# as14120_x31_fpga_ddr.net
KiCad netlist of a schematic drawn in Altium Designer
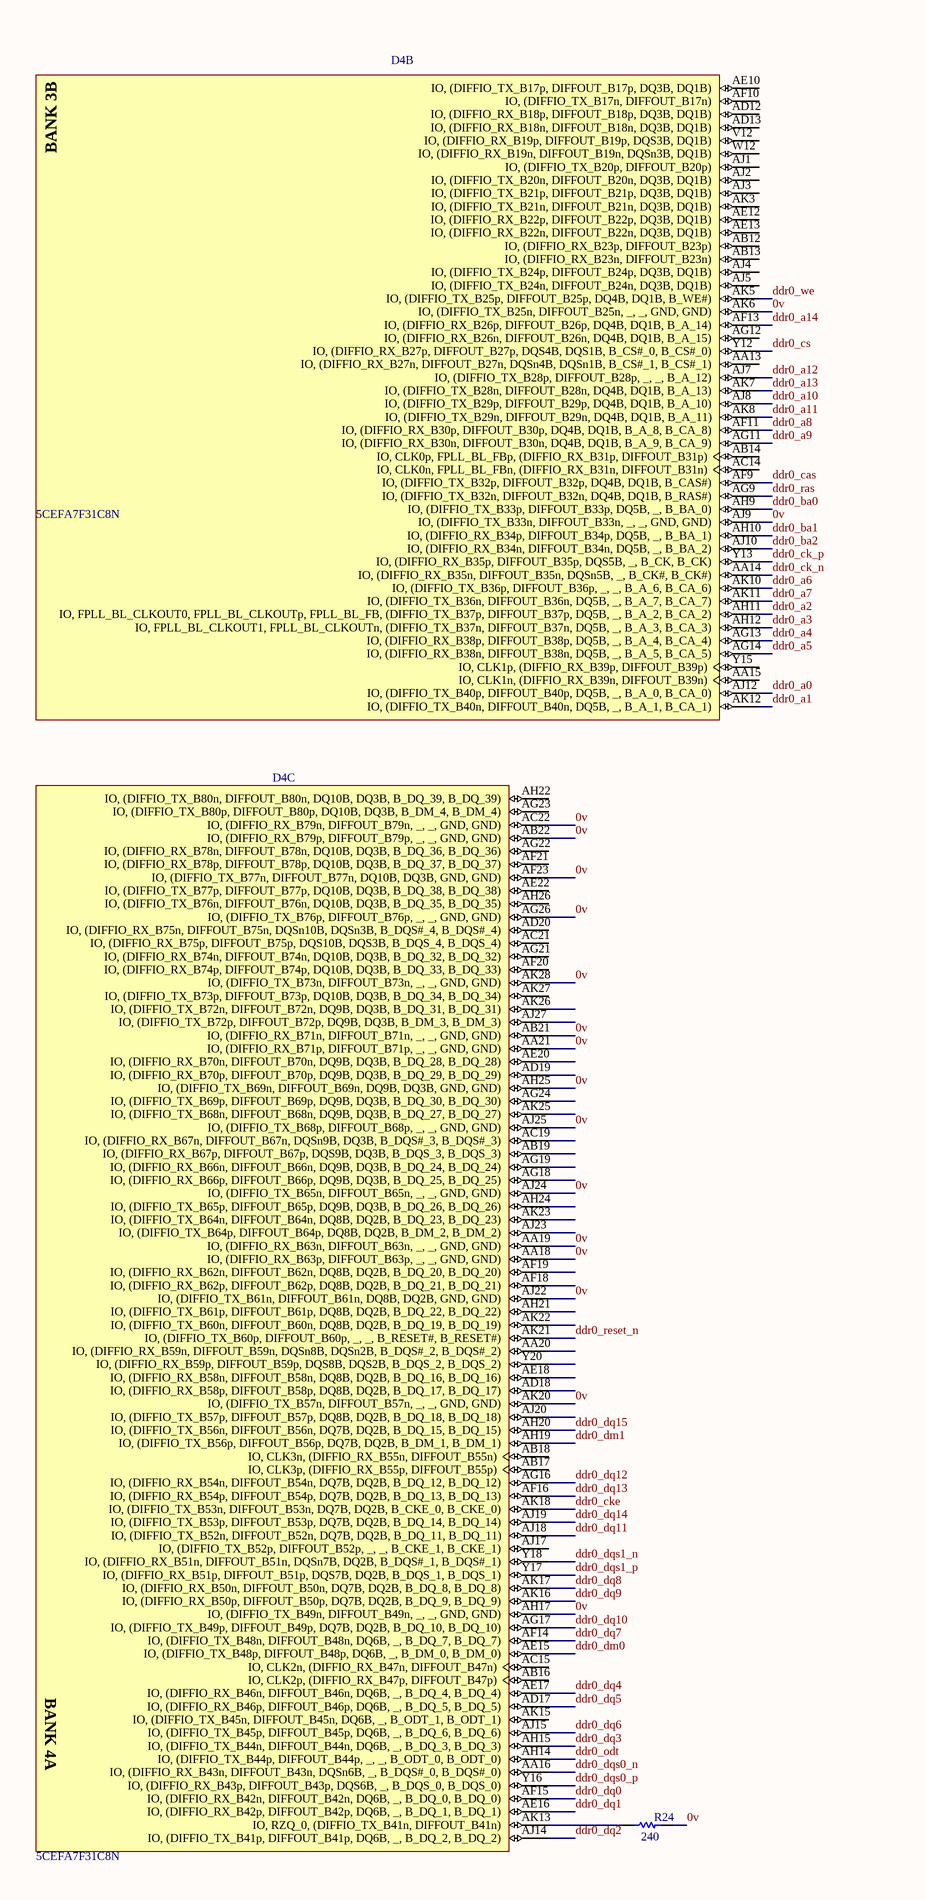
[diagram p0: as14120_x31_fpga_ddr.SchDoc, left]
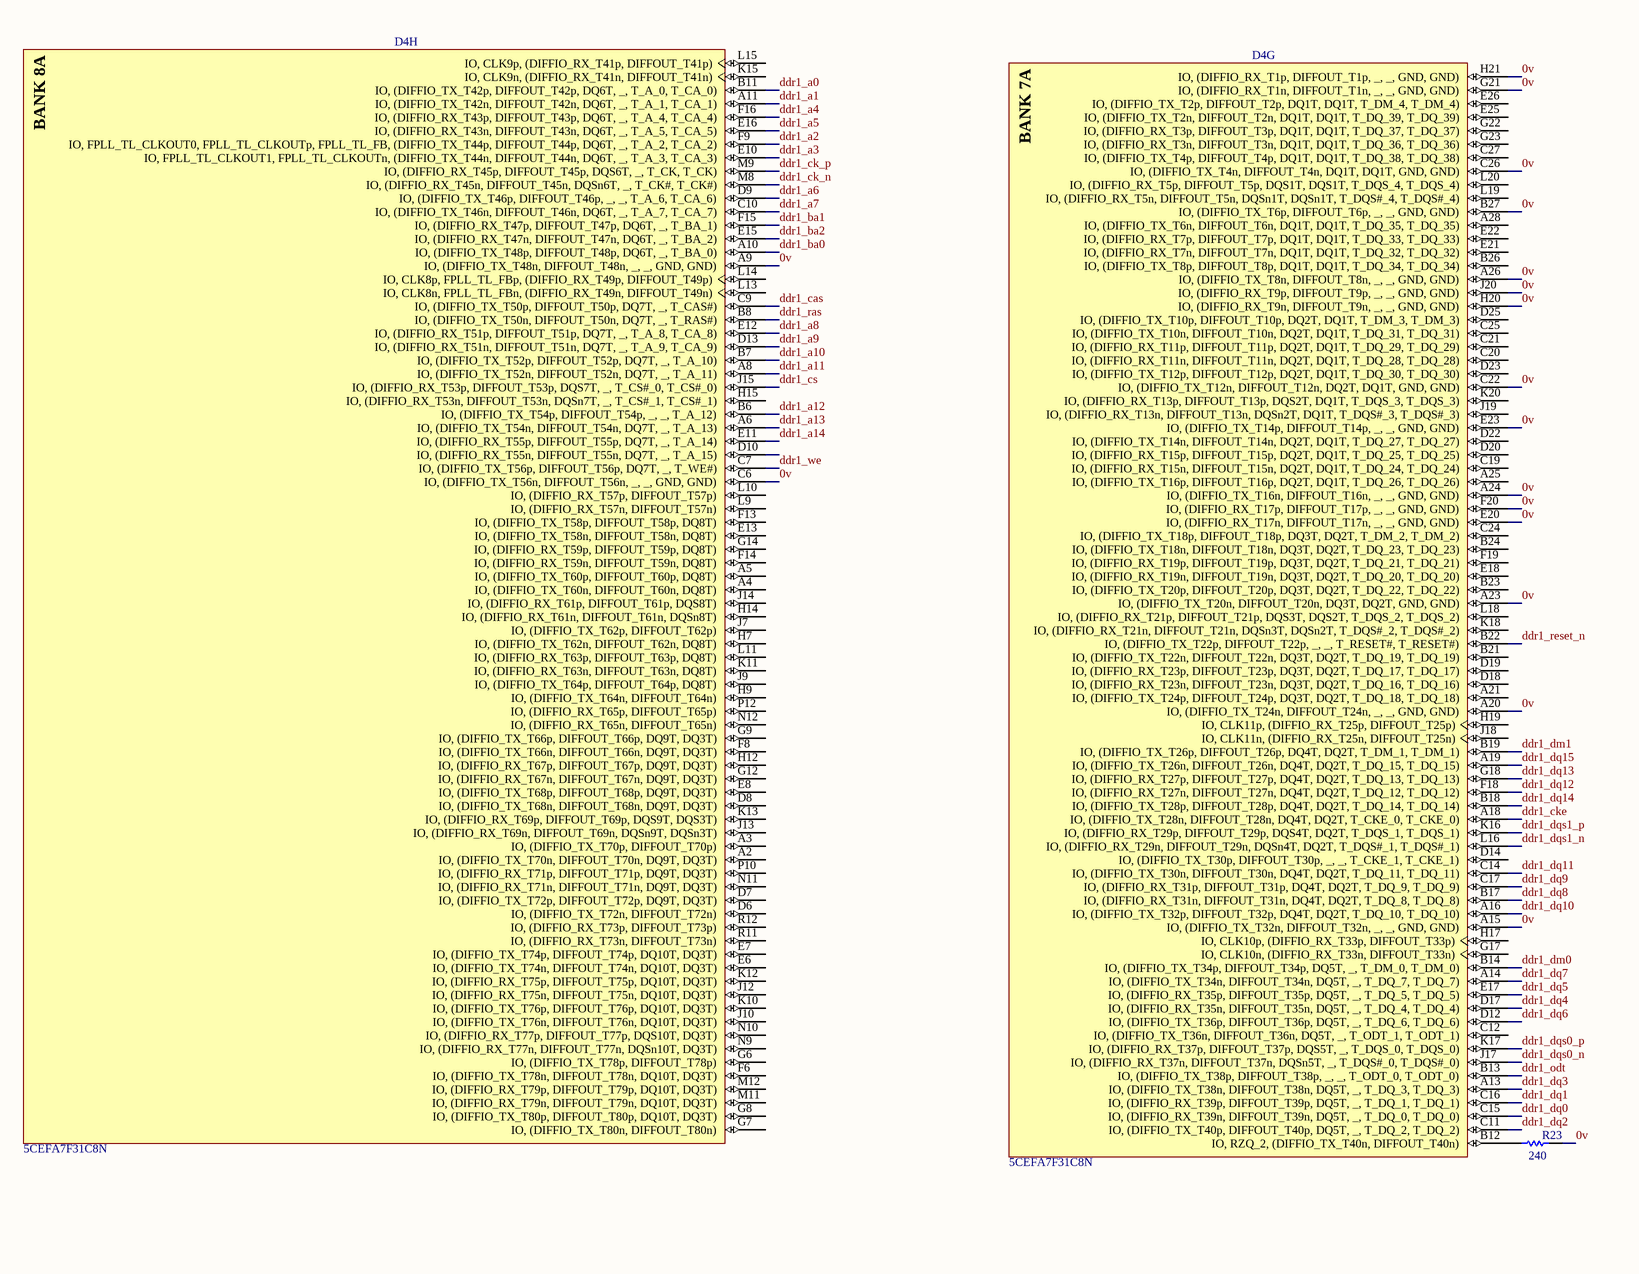
[diagram p1: as14120_x31_fpga_ddr.SchDoc, right]

(export (version "E")
  (design (tool "Eeschema 10.0.6"))
  (components
    (comp (ref "D4")
      (value "5CEFA7F31C8N")
      (footprint "ALTR-896-FBGA-2000A")
      (fields (field (name "MANUFACTURER") "Altera"))
      (libsource (lib "") (part "5CEFA7F31C8N_1"))
    )
    (comp (ref "R23")
      (value "240")
      (footprint "RESC0805(2012)_L")
      (description "1K 0.125W 1% 0805 (2012 Metric)  SMD")
      (fields (field (name "TOLERANCE") "1 %") (field (name "POWER") "0.125 W"))
      (libsource (lib "as14120") (part "RES_0805"))
    )
    (comp (ref "R24")
      (value "240")
      (footprint "RESC0805(2012)_L")
      (description "1K 0.125W 1% 0805 (2012 Metric)  SMD")
      (fields (field (name "TOLERANCE") "1 %") (field (name "POWER") "0.125 W"))
      (libsource (lib "as14120") (part "RES_0805"))
    )
  )
  (nets
    (net (code "1") (name "/0v") (class "Default")
      (node (ref "D4") (pin "A15") (pinfunction "IO,_(DIFFIO_TX_T32n,_DIFFOUT_T32n,__,__,_GND,_GND)_A15") (pintype "bidirectional"))
      (node (ref "D4") (pin "A20") (pinfunction "IO,_(DIFFIO_TX_T24n,_DIFFOUT_T24n,__,__,_GND,_GND)_A20") (pintype "bidirectional"))
      (node (ref "D4") (pin "A23") (pinfunction "IO,_(DIFFIO_TX_T20n,_DIFFOUT_T20n,_DQ3T,_DQ2T,_GND,_GND)_A23") (pintype "bidirectional"))
      (node (ref "D4") (pin "A24") (pinfunction "IO,_(DIFFIO_TX_T16n,_DIFFOUT_T16n,__,__,_GND,_GND)_A24") (pintype "bidirectional"))
      (node (ref "D4") (pin "A26") (pinfunction "IO,_(DIFFIO_TX_T8n,_DIFFOUT_T8n,__,__,_GND,_GND)_A26") (pintype "bidirectional"))
      (node (ref "D4") (pin "A9") (pinfunction "IO,_(DIFFIO_TX_T48n,_DIFFOUT_T48n,__,__,_GND,_GND)_A9") (pintype "bidirectional"))
      (node (ref "D4") (pin "AA18") (pinfunction "IO,_(DIFFIO_RX_B63p,_DIFFOUT_B63p,__,__,_GND,_GND)_AA18") (pintype "bidirectional"))
      (node (ref "D4") (pin "AA19") (pinfunction "IO,_(DIFFIO_RX_B63n,_DIFFOUT_B63n,__,__,_GND,_GND)_AA19") (pintype "bidirectional"))
      (node (ref "D4") (pin "AA21") (pinfunction "IO,_(DIFFIO_RX_B71p,_DIFFOUT_B71p,__,__,_GND,_GND)_AA21") (pintype "bidirectional"))
      (node (ref "D4") (pin "AB21") (pinfunction "IO,_(DIFFIO_RX_B71n,_DIFFOUT_B71n,__,__,_GND,_GND)_AB21") (pintype "bidirectional"))
      (node (ref "D4") (pin "AB22") (pinfunction "IO,_(DIFFIO_RX_B79p,_DIFFOUT_B79p,__,__,_GND,_GND)_AB22") (pintype "bidirectional"))
      (node (ref "D4") (pin "AC22") (pinfunction "IO,_(DIFFIO_RX_B79n,_DIFFOUT_B79n,__,__,_GND,_GND)_AC22") (pintype "bidirectional"))
      (node (ref "D4") (pin "AF23") (pinfunction "IO,_(DIFFIO_TX_B77n,_DIFFOUT_B77n,_DQ10B,_DQ3B,_GND,_GND)_AF23") (pintype "bidirectional"))
      (node (ref "D4") (pin "AG26") (pinfunction "IO,_(DIFFIO_TX_B76p,_DIFFOUT_B76p,__,__,_GND,_GND)_AG26") (pintype "bidirectional"))
      (node (ref "D4") (pin "AH17") (pinfunction "IO,_(DIFFIO_TX_B49n,_DIFFOUT_B49n,__,__,_GND,_GND)_AH17") (pintype "bidirectional"))
      (node (ref "D4") (pin "AH25") (pinfunction "IO,_(DIFFIO_TX_B69n,_DIFFOUT_B69n,_DQ9B,_DQ3B,_GND,_GND)_AH25") (pintype "bidirectional"))
      (node (ref "D4") (pin "AJ22") (pinfunction "IO,_(DIFFIO_TX_B61n,_DIFFOUT_B61n,_DQ8B,_DQ2B,_GND,_GND)_AJ22") (pintype "bidirectional"))
      (node (ref "D4") (pin "AJ24") (pinfunction "IO,_(DIFFIO_TX_B65n,_DIFFOUT_B65n,__,__,_GND,_GND)_AJ24") (pintype "bidirectional"))
      (node (ref "D4") (pin "AJ25") (pinfunction "IO,_(DIFFIO_TX_B68p,_DIFFOUT_B68p,__,__,_GND,_GND)_AJ25") (pintype "bidirectional"))
      (node (ref "D4") (pin "AJ9") (pinfunction "IO,_(DIFFIO_TX_B33n,_DIFFOUT_B33n,__,__,_GND,_GND)_AJ9") (pintype "bidirectional"))
      (node (ref "D4") (pin "AK20") (pinfunction "IO,_(DIFFIO_TX_B57n,_DIFFOUT_B57n,__,__,_GND,_GND)_AK20") (pintype "bidirectional"))
      (node (ref "D4") (pin "AK28") (pinfunction "IO,_(DIFFIO_TX_B73n,_DIFFOUT_B73n,__,__,_GND,_GND)_AK28") (pintype "bidirectional"))
      (node (ref "D4") (pin "AK6") (pinfunction "IO,_(DIFFIO_TX_B25n,_DIFFOUT_B25n,__,__,_GND,_GND)_AK6") (pintype "bidirectional"))
      (node (ref "D4") (pin "B27") (pinfunction "IO,_(DIFFIO_TX_T6p,_DIFFOUT_T6p,__,__,_GND,_GND)_B27") (pintype "bidirectional"))
      (node (ref "D4") (pin "C22") (pinfunction "IO,_(DIFFIO_TX_T12n,_DIFFOUT_T12n,_DQ2T,_DQ1T,_GND,_GND)_C22") (pintype "bidirectional"))
      (node (ref "D4") (pin "C26") (pinfunction "IO,_(DIFFIO_TX_T4n,_DIFFOUT_T4n,_DQ1T,_DQ1T,_GND,_GND)_C26") (pintype "bidirectional"))
      (node (ref "D4") (pin "C6") (pinfunction "IO,_(DIFFIO_TX_T56n,_DIFFOUT_T56n,__,__,_GND,_GND)_C6") (pintype "bidirectional"))
      (node (ref "D4") (pin "E20") (pinfunction "IO,_(DIFFIO_RX_T17n,_DIFFOUT_T17n,__,__,_GND,_GND)_E20") (pintype "bidirectional"))
      (node (ref "D4") (pin "E23") (pinfunction "IO,_(DIFFIO_TX_T14p,_DIFFOUT_T14p,__,__,_GND,_GND)_E23") (pintype "bidirectional"))
      (node (ref "D4") (pin "F20") (pinfunction "IO,_(DIFFIO_RX_T17p,_DIFFOUT_T17p,__,__,_GND,_GND)_F20") (pintype "bidirectional"))
      (node (ref "D4") (pin "G21") (pinfunction "IO,_(DIFFIO_RX_T1n,_DIFFOUT_T1n,__,__,_GND,_GND)_G21") (pintype "bidirectional"))
      (node (ref "D4") (pin "H20") (pinfunction "IO,_(DIFFIO_RX_T9n,_DIFFOUT_T9n,__,__,_GND,_GND)_H20") (pintype "bidirectional"))
      (node (ref "D4") (pin "H21") (pinfunction "IO,_(DIFFIO_RX_T1p,_DIFFOUT_T1p,__,__,_GND,_GND)_H21") (pintype "bidirectional"))
      (node (ref "D4") (pin "J20") (pinfunction "IO,_(DIFFIO_RX_T9p,_DIFFOUT_T9p,__,__,_GND,_GND)_J20") (pintype "bidirectional"))
      (node (ref "R23") (pin "2") (pinfunction "2_2") (pintype "passive"))
      (node (ref "R24") (pin "2") (pinfunction "2_2") (pintype "passive"))
    )
    (net (code "2") (name "/ddr0_a0") (class "Default")
      (node (ref "D4") (pin "AJ12") (pinfunction "IO,_(DIFFIO_TX_B40p,_DIFFOUT_B40p,_DQ5B,__,_B_A_0,_B_CA_0)_AJ12") (pintype "bidirectional"))
    )
    (net (code "3") (name "/ddr0_a1") (class "Default")
      (node (ref "D4") (pin "AK12") (pinfunction "IO,_(DIFFIO_TX_B40n,_DIFFOUT_B40n,_DQ5B,__,_B_A_1,_B_CA_1)_AK12") (pintype "bidirectional"))
    )
    (net (code "4") (name "/ddr0_a2") (class "Default")
      (node (ref "D4") (pin "AH11") (pinfunction "IO,_FPLL_BL_CLKOUT0,_FPLL_BL_CLKOUTp,_FPLL_BL_FB,_(DIFFIO_TX_B37p,_DIFFOUT_B37p,_DQ5B,__,_B_A_2,_B_CA_2)_AH11") (pintype "bidirectional"))
    )
    (net (code "5") (name "/ddr0_a3") (class "Default")
      (node (ref "D4") (pin "AH12") (pinfunction "IO,_FPLL_BL_CLKOUT1,_FPLL_BL_CLKOUTn,_(DIFFIO_TX_B37n,_DIFFOUT_B37n,_DQ5B,__,_B_A_3,_B_CA_3)_AH12") (pintype "bidirectional"))
    )
    (net (code "6") (name "/ddr0_a4") (class "Default")
      (node (ref "D4") (pin "AG13") (pinfunction "IO,_(DIFFIO_RX_B38p,_DIFFOUT_B38p,_DQ5B,__,_B_A_4,_B_CA_4)_AG13") (pintype "bidirectional"))
    )
    (net (code "7") (name "/ddr0_a5") (class "Default")
      (node (ref "D4") (pin "AG14") (pinfunction "IO,_(DIFFIO_RX_B38n,_DIFFOUT_B38n,_DQ5B,__,_B_A_5,_B_CA_5)_AG14") (pintype "bidirectional"))
    )
    (net (code "8") (name "/ddr0_a6") (class "Default")
      (node (ref "D4") (pin "AK10") (pinfunction "IO,_(DIFFIO_TX_B36p,_DIFFOUT_B36p,__,__,_B_A_6,_B_CA_6)_AK10") (pintype "bidirectional"))
    )
    (net (code "9") (name "/ddr0_a7") (class "Default")
      (node (ref "D4") (pin "AK11") (pinfunction "IO,_(DIFFIO_TX_B36n,_DIFFOUT_B36n,_DQ5B,__,_B_A_7,_B_CA_7)_AK11") (pintype "bidirectional"))
    )
    (net (code "10") (name "/ddr0_a8") (class "Default")
      (node (ref "D4") (pin "AF11") (pinfunction "IO,_(DIFFIO_RX_B30p,_DIFFOUT_B30p,_DQ4B,_DQ1B,_B_A_8,_B_CA_8)_AF11") (pintype "bidirectional"))
    )
    (net (code "11") (name "/ddr0_a9") (class "Default")
      (node (ref "D4") (pin "AG11") (pinfunction "IO,_(DIFFIO_RX_B30n,_DIFFOUT_B30n,_DQ4B,_DQ1B,_B_A_9,_B_CA_9)_AG11") (pintype "bidirectional"))
    )
    (net (code "12") (name "/ddr0_a10") (class "Default")
      (node (ref "D4") (pin "AJ8") (pinfunction "IO,_(DIFFIO_TX_B29p,_DIFFOUT_B29p,_DQ4B,_DQ1B,_B_A_10)_AJ8") (pintype "bidirectional"))
    )
    (net (code "13") (name "/ddr0_a11") (class "Default")
      (node (ref "D4") (pin "AK8") (pinfunction "IO,_(DIFFIO_TX_B29n,_DIFFOUT_B29n,_DQ4B,_DQ1B,_B_A_11)_AK8") (pintype "bidirectional"))
    )
    (net (code "14") (name "/ddr0_a12") (class "Default")
      (node (ref "D4") (pin "AJ7") (pinfunction "IO,_(DIFFIO_TX_B28p,_DIFFOUT_B28p,__,__,_B_A_12)_AJ7") (pintype "bidirectional"))
    )
    (net (code "15") (name "/ddr0_a13") (class "Default")
      (node (ref "D4") (pin "AK7") (pinfunction "IO,_(DIFFIO_TX_B28n,_DIFFOUT_B28n,_DQ4B,_DQ1B,_B_A_13)_AK7") (pintype "bidirectional"))
    )
    (net (code "16") (name "/ddr0_a14") (class "Default")
      (node (ref "D4") (pin "AF13") (pinfunction "IO,_(DIFFIO_RX_B26p,_DIFFOUT_B26p,_DQ4B,_DQ1B,_B_A_14)_AF13") (pintype "bidirectional"))
    )
    (net (code "17") (name "/ddr0_ba0") (class "Default")
      (node (ref "D4") (pin "AH9") (pinfunction "IO,_(DIFFIO_TX_B33p,_DIFFOUT_B33p,_DQ5B,__,_B_BA_0)_AH9") (pintype "bidirectional"))
    )
    (net (code "18") (name "/ddr0_ba1") (class "Default")
      (node (ref "D4") (pin "AH10") (pinfunction "IO,_(DIFFIO_RX_B34p,_DIFFOUT_B34p,_DQ5B,__,_B_BA_1)_AH10") (pintype "bidirectional"))
    )
    (net (code "19") (name "/ddr0_ba2") (class "Default")
      (node (ref "D4") (pin "AJ10") (pinfunction "IO,_(DIFFIO_RX_B34n,_DIFFOUT_B34n,_DQ5B,__,_B_BA_2)_AJ10") (pintype "bidirectional"))
    )
    (net (code "20") (name "/ddr0_cas") (class "Default")
      (node (ref "D4") (pin "AF9") (pinfunction "IO,_(DIFFIO_TX_B32p,_DIFFOUT_B32p,_DQ4B,_DQ1B,_B_CAS#)_AF9") (pintype "bidirectional"))
    )
    (net (code "21") (name "/ddr0_ck_n") (class "Default")
      (node (ref "D4") (pin "AA14") (pinfunction "IO,_(DIFFIO_RX_B35n,_DIFFOUT_B35n,_DQSn5B,__,_B_CK#,_B_CK#)_AA14") (pintype "bidirectional"))
    )
    (net (code "22") (name "/ddr0_ck_p") (class "Default")
      (node (ref "D4") (pin "Y13") (pinfunction "IO,_(DIFFIO_RX_B35p,_DIFFOUT_B35p,_DQS5B,__,_B_CK,_B_CK)_Y13") (pintype "bidirectional"))
    )
    (net (code "23") (name "/ddr0_cke") (class "Default")
      (node (ref "D4") (pin "AK18") (pinfunction "IO,_(DIFFIO_TX_B53n,_DIFFOUT_B53n,_DQ7B,_DQ2B,_B_CKE_0,_B_CKE_0)_AK18") (pintype "bidirectional"))
    )
    (net (code "24") (name "/ddr0_cs") (class "Default")
      (node (ref "D4") (pin "Y12") (pinfunction "IO,_(DIFFIO_RX_B27p,_DIFFOUT_B27p,_DQS4B,_DQS1B,_B_CS#_0,_B_CS#_0)_Y12") (pintype "bidirectional"))
    )
    (net (code "25") (name "/ddr0_dm0") (class "Default")
      (node (ref "D4") (pin "AE15") (pinfunction "IO,_(DIFFIO_TX_B48p,_DIFFOUT_B48p,_DQ6B,__,_B_DM_0,_B_DM_0)_AE15") (pintype "bidirectional"))
    )
    (net (code "26") (name "/ddr0_dm1") (class "Default")
      (node (ref "D4") (pin "AH19") (pinfunction "IO,_(DIFFIO_TX_B56p,_DIFFOUT_B56p,_DQ7B,_DQ2B,_B_DM_1,_B_DM_1)_AH19") (pintype "bidirectional"))
    )
    (net (code "27") (name "/ddr0_dq0") (class "Default")
      (node (ref "D4") (pin "AF15") (pinfunction "IO,_(DIFFIO_RX_B42n,_DIFFOUT_B42n,_DQ6B,__,_B_DQ_0,_B_DQ_0)_AF15") (pintype "bidirectional"))
    )
    (net (code "28") (name "/ddr0_dq1") (class "Default")
      (node (ref "D4") (pin "AE16") (pinfunction "IO,_(DIFFIO_RX_B42p,_DIFFOUT_B42p,_DQ6B,__,_B_DQ_1,_B_DQ_1)_AE16") (pintype "bidirectional"))
    )
    (net (code "29") (name "/ddr0_dq2") (class "Default")
      (node (ref "D4") (pin "AJ14") (pinfunction "IO,_(DIFFIO_TX_B41p,_DIFFOUT_B41p,_DQ6B,__,_B_DQ_2,_B_DQ_2)_AJ14") (pintype "bidirectional"))
    )
    (net (code "30") (name "/ddr0_dq3") (class "Default")
      (node (ref "D4") (pin "AH15") (pinfunction "IO,_(DIFFIO_TX_B44n,_DIFFOUT_B44n,_DQ6B,__,_B_DQ_3,_B_DQ_3)_AH15") (pintype "bidirectional"))
    )
    (net (code "31") (name "/ddr0_dq4") (class "Default")
      (node (ref "D4") (pin "AE17") (pinfunction "IO,_(DIFFIO_RX_B46n,_DIFFOUT_B46n,_DQ6B,__,_B_DQ_4,_B_DQ_4)_AE17") (pintype "bidirectional"))
    )
    (net (code "32") (name "/ddr0_dq5") (class "Default")
      (node (ref "D4") (pin "AD17") (pinfunction "IO,_(DIFFIO_RX_B46p,_DIFFOUT_B46p,_DQ6B,__,_B_DQ_5,_B_DQ_5)_AD17") (pintype "bidirectional"))
    )
    (net (code "33") (name "/ddr0_dq6") (class "Default")
      (node (ref "D4") (pin "AJ15") (pinfunction "IO,_(DIFFIO_TX_B45p,_DIFFOUT_B45p,_DQ6B,__,_B_DQ_6,_B_DQ_6)_AJ15") (pintype "bidirectional"))
    )
    (net (code "34") (name "/ddr0_dq7") (class "Default")
      (node (ref "D4") (pin "AF14") (pinfunction "IO,_(DIFFIO_TX_B48n,_DIFFOUT_B48n,_DQ6B,__,_B_DQ_7,_B_DQ_7)_AF14") (pintype "bidirectional"))
    )
    (net (code "35") (name "/ddr0_dq8") (class "Default")
      (node (ref "D4") (pin "AK17") (pinfunction "IO,_(DIFFIO_RX_B50n,_DIFFOUT_B50n,_DQ7B,_DQ2B,_B_DQ_8,_B_DQ_8)_AK17") (pintype "bidirectional"))
    )
    (net (code "36") (name "/ddr0_dq9") (class "Default")
      (node (ref "D4") (pin "AK16") (pinfunction "IO,_(DIFFIO_RX_B50p,_DIFFOUT_B50p,_DQ7B,_DQ2B,_B_DQ_9,_B_DQ_9)_AK16") (pintype "bidirectional"))
    )
    (net (code "37") (name "/ddr0_dq10") (class "Default")
      (node (ref "D4") (pin "AG17") (pinfunction "IO,_(DIFFIO_TX_B49p,_DIFFOUT_B49p,_DQ7B,_DQ2B,_B_DQ_10,_B_DQ_10)_AG17") (pintype "bidirectional"))
    )
    (net (code "38") (name "/ddr0_dq11") (class "Default")
      (node (ref "D4") (pin "AJ18") (pinfunction "IO,_(DIFFIO_TX_B52n,_DIFFOUT_B52n,_DQ7B,_DQ2B,_B_DQ_11,_B_DQ_11)_AJ18") (pintype "bidirectional"))
    )
    (net (code "39") (name "/ddr0_dq12") (class "Default")
      (node (ref "D4") (pin "AG16") (pinfunction "IO,_(DIFFIO_RX_B54n,_DIFFOUT_B54n,_DQ7B,_DQ2B,_B_DQ_12,_B_DQ_12)_AG16") (pintype "bidirectional"))
    )
    (net (code "40") (name "/ddr0_dq13") (class "Default")
      (node (ref "D4") (pin "AF16") (pinfunction "IO,_(DIFFIO_RX_B54p,_DIFFOUT_B54p,_DQ7B,_DQ2B,_B_DQ_13,_B_DQ_13)_AF16") (pintype "bidirectional"))
    )
    (net (code "41") (name "/ddr0_dq14") (class "Default")
      (node (ref "D4") (pin "AJ19") (pinfunction "IO,_(DIFFIO_TX_B53p,_DIFFOUT_B53p,_DQ7B,_DQ2B,_B_DQ_14,_B_DQ_14)_AJ19") (pintype "bidirectional"))
    )
    (net (code "42") (name "/ddr0_dq15") (class "Default")
      (node (ref "D4") (pin "AH20") (pinfunction "IO,_(DIFFIO_TX_B56n,_DIFFOUT_B56n,_DQ7B,_DQ2B,_B_DQ_15,_B_DQ_15)_AH20") (pintype "bidirectional"))
    )
    (net (code "43") (name "/ddr0_dqs0_n") (class "Default")
      (node (ref "D4") (pin "AA16") (pinfunction "IO,_(DIFFIO_RX_B43n,_DIFFOUT_B43n,_DQSn6B,__,_B_DQS#_0,_B_DQS#_0)_AA16") (pintype "bidirectional"))
    )
    (net (code "44") (name "/ddr0_dqs0_p") (class "Default")
      (node (ref "D4") (pin "Y16") (pinfunction "IO,_(DIFFIO_RX_B43p,_DIFFOUT_B43p,_DQS6B,__,_B_DQS_0,_B_DQS_0)_Y16") (pintype "bidirectional"))
    )
    (net (code "45") (name "/ddr0_dqs1_n") (class "Default")
      (node (ref "D4") (pin "Y18") (pinfunction "IO,_(DIFFIO_RX_B51n,_DIFFOUT_B51n,_DQSn7B,_DQ2B,_B_DQS#_1,_B_DQS#_1)_Y18") (pintype "bidirectional"))
    )
    (net (code "46") (name "/ddr0_dqs1_p") (class "Default")
      (node (ref "D4") (pin "Y17") (pinfunction "IO,_(DIFFIO_RX_B51p,_DIFFOUT_B51p,_DQS7B,_DQ2B,_B_DQS_1,_B_DQS_1)_Y17") (pintype "bidirectional"))
    )
    (net (code "47") (name "/ddr0_odt") (class "Default")
      (node (ref "D4") (pin "AH14") (pinfunction "IO,_(DIFFIO_TX_B44p,_DIFFOUT_B44p,__,__,_B_ODT_0,_B_ODT_0)_AH14") (pintype "bidirectional"))
    )
    (net (code "48") (name "/ddr0_ras") (class "Default")
      (node (ref "D4") (pin "AG9") (pinfunction "IO,_(DIFFIO_TX_B32n,_DIFFOUT_B32n,_DQ4B,_DQ1B,_B_RAS#)_AG9") (pintype "bidirectional"))
    )
    (net (code "49") (name "/ddr0_reset_n") (class "Default")
      (node (ref "D4") (pin "AK21") (pinfunction "IO,_(DIFFIO_TX_B60p,_DIFFOUT_B60p,__,__,_B_RESET#,_B_RESET#)_AK21") (pintype "bidirectional"))
    )
    (net (code "50") (name "/ddr0_we") (class "Default")
      (node (ref "D4") (pin "AK5") (pinfunction "IO,_(DIFFIO_TX_B25p,_DIFFOUT_B25p,_DQ4B,_DQ1B,_B_WE#)_AK5") (pintype "bidirectional"))
    )
    (net (code "51") (name "/ddr1_a0") (class "Default")
      (node (ref "D4") (pin "B11") (pinfunction "IO,_(DIFFIO_TX_T42p,_DIFFOUT_T42p,_DQ6T,__,_T_A_0,_T_CA_0)_B11") (pintype "bidirectional"))
    )
    (net (code "52") (name "/ddr1_a1") (class "Default")
      (node (ref "D4") (pin "A11") (pinfunction "IO,_(DIFFIO_TX_T42n,_DIFFOUT_T42n,_DQ6T,__,_T_A_1,_T_CA_1)_A11") (pintype "bidirectional"))
    )
    (net (code "53") (name "/ddr1_a2") (class "Default")
      (node (ref "D4") (pin "F9") (pinfunction "IO,_FPLL_TL_CLKOUT0,_FPLL_TL_CLKOUTp,_FPLL_TL_FB,_(DIFFIO_TX_T44p,_DIFFOUT_T44p,_DQ6T,__,_T_A_2,_T_CA_2)_F9") (pintype "bidirectional"))
    )
    (net (code "54") (name "/ddr1_a3") (class "Default")
      (node (ref "D4") (pin "E10") (pinfunction "IO,_FPLL_TL_CLKOUT1,_FPLL_TL_CLKOUTn,_(DIFFIO_TX_T44n,_DIFFOUT_T44n,_DQ6T,__,_T_A_3,_T_CA_3)_E10") (pintype "bidirectional"))
    )
    (net (code "55") (name "/ddr1_a4") (class "Default")
      (node (ref "D4") (pin "F16") (pinfunction "IO,_(DIFFIO_RX_T43p,_DIFFOUT_T43p,_DQ6T,__,_T_A_4,_T_CA_4)_F16") (pintype "bidirectional"))
    )
    (net (code "56") (name "/ddr1_a5") (class "Default")
      (node (ref "D4") (pin "E16") (pinfunction "IO,_(DIFFIO_RX_T43n,_DIFFOUT_T43n,_DQ6T,__,_T_A_5,_T_CA_5)_E16") (pintype "bidirectional"))
    )
    (net (code "57") (name "/ddr1_a6") (class "Default")
      (node (ref "D4") (pin "D9") (pinfunction "IO,_(DIFFIO_TX_T46p,_DIFFOUT_T46p,__,__,_T_A_6,_T_CA_6)_D9") (pintype "bidirectional"))
    )
    (net (code "58") (name "/ddr1_a7") (class "Default")
      (node (ref "D4") (pin "C10") (pinfunction "IO,_(DIFFIO_TX_T46n,_DIFFOUT_T46n,_DQ6T,__,_T_A_7,_T_CA_7)_C10") (pintype "bidirectional"))
    )
    (net (code "59") (name "/ddr1_a8") (class "Default")
      (node (ref "D4") (pin "E12") (pinfunction "IO,_(DIFFIO_RX_T51p,_DIFFOUT_T51p,_DQ7T,__,_T_A_8,_T_CA_8)_E12") (pintype "bidirectional"))
    )
    (net (code "60") (name "/ddr1_a9") (class "Default")
      (node (ref "D4") (pin "D13") (pinfunction "IO,_(DIFFIO_RX_T51n,_DIFFOUT_T51n,_DQ7T,__,_T_A_9,_T_CA_9)_D13") (pintype "bidirectional"))
    )
    (net (code "61") (name "/ddr1_a10") (class "Default")
      (node (ref "D4") (pin "B7") (pinfunction "IO,_(DIFFIO_TX_T52p,_DIFFOUT_T52p,_DQ7T,__,_T_A_10)_B7") (pintype "bidirectional"))
    )
    (net (code "62") (name "/ddr1_a11") (class "Default")
      (node (ref "D4") (pin "A8") (pinfunction "IO,_(DIFFIO_TX_T52n,_DIFFOUT_T52n,_DQ7T,__,_T_A_11)_A8") (pintype "bidirectional"))
    )
    (net (code "63") (name "/ddr1_a12") (class "Default")
      (node (ref "D4") (pin "B6") (pinfunction "IO,_(DIFFIO_TX_T54p,_DIFFOUT_T54p,__,__,_T_A_12)_B6") (pintype "bidirectional"))
    )
    (net (code "64") (name "/ddr1_a13") (class "Default")
      (node (ref "D4") (pin "A6") (pinfunction "IO,_(DIFFIO_TX_T54n,_DIFFOUT_T54n,_DQ7T,__,_T_A_13)_A6") (pintype "bidirectional"))
    )
    (net (code "65") (name "/ddr1_a14") (class "Default")
      (node (ref "D4") (pin "E11") (pinfunction "IO,_(DIFFIO_RX_T55p,_DIFFOUT_T55p,_DQ7T,__,_T_A_14)_E11") (pintype "bidirectional"))
    )
    (net (code "66") (name "/ddr1_ba0") (class "Default")
      (node (ref "D4") (pin "A10") (pinfunction "IO,_(DIFFIO_TX_T48p,_DIFFOUT_T48p,_DQ6T,__,_T_BA_0)_A10") (pintype "bidirectional"))
    )
    (net (code "67") (name "/ddr1_ba1") (class "Default")
      (node (ref "D4") (pin "F15") (pinfunction "IO,_(DIFFIO_RX_T47p,_DIFFOUT_T47p,_DQ6T,__,_T_BA_1)_F15") (pintype "bidirectional"))
    )
    (net (code "68") (name "/ddr1_ba2") (class "Default")
      (node (ref "D4") (pin "E15") (pinfunction "IO,_(DIFFIO_RX_T47n,_DIFFOUT_T47n,_DQ6T,__,_T_BA_2)_E15") (pintype "bidirectional"))
    )
    (net (code "69") (name "/ddr1_cas") (class "Default")
      (node (ref "D4") (pin "C9") (pinfunction "IO,_(DIFFIO_TX_T50p,_DIFFOUT_T50p,_DQ7T,__,_T_CAS#)_C9") (pintype "bidirectional"))
    )
    (net (code "70") (name "/ddr1_ck_n") (class "Default")
      (node (ref "D4") (pin "M8") (pinfunction "IO,_(DIFFIO_RX_T45n,_DIFFOUT_T45n,_DQSn6T,__,_T_CK#,_T_CK#)_M8") (pintype "bidirectional"))
    )
    (net (code "71") (name "/ddr1_ck_p") (class "Default")
      (node (ref "D4") (pin "M9") (pinfunction "IO,_(DIFFIO_RX_T45p,_DIFFOUT_T45p,_DQS6T,__,_T_CK,_T_CK)_M9") (pintype "bidirectional"))
    )
    (net (code "72") (name "/ddr1_cke") (class "Default")
      (node (ref "D4") (pin "A18") (pinfunction "IO,_(DIFFIO_TX_T28n,_DIFFOUT_T28n,_DQ4T,_DQ2T,_T_CKE_0,_T_CKE_0)_A18") (pintype "bidirectional"))
    )
    (net (code "73") (name "/ddr1_cs") (class "Default")
      (node (ref "D4") (pin "J15") (pinfunction "IO,_(DIFFIO_RX_T53p,_DIFFOUT_T53p,_DQS7T,__,_T_CS#_0,_T_CS#_0)_J15") (pintype "bidirectional"))
    )
    (net (code "74") (name "/ddr1_dm0") (class "Default")
      (node (ref "D4") (pin "B14") (pinfunction "IO,_(DIFFIO_TX_T34p,_DIFFOUT_T34p,_DQ5T,__,_T_DM_0,_T_DM_0)_B14") (pintype "bidirectional"))
    )
    (net (code "75") (name "/ddr1_dm1") (class "Default")
      (node (ref "D4") (pin "B19") (pinfunction "IO,_(DIFFIO_TX_T26p,_DIFFOUT_T26p,_DQ4T,_DQ2T,_T_DM_1,_T_DM_1)_B19") (pintype "bidirectional"))
    )
    (net (code "76") (name "/ddr1_dq0") (class "Default")
      (node (ref "D4") (pin "C15") (pinfunction "IO,_(DIFFIO_RX_T39n,_DIFFOUT_T39n,_DQ5T,__,_T_DQ_0,_T_DQ_0)_C15") (pintype "bidirectional"))
    )
    (net (code "77") (name "/ddr1_dq1") (class "Default")
      (node (ref "D4") (pin "C16") (pinfunction "IO,_(DIFFIO_RX_T39p,_DIFFOUT_T39p,_DQ5T,__,_T_DQ_1,_T_DQ_1)_C16") (pintype "bidirectional"))
    )
    (net (code "78") (name "/ddr1_dq2") (class "Default")
      (node (ref "D4") (pin "C11") (pinfunction "IO,_(DIFFIO_TX_T40p,_DIFFOUT_T40p,_DQ5T,__,_T_DQ_2,_T_DQ_2)_C11") (pintype "bidirectional"))
    )
    (net (code "79") (name "/ddr1_dq3") (class "Default")
      (node (ref "D4") (pin "A13") (pinfunction "IO,_(DIFFIO_TX_T38n,_DIFFOUT_T38n,_DQ5T,__,_T_DQ_3,_T_DQ_3)_A13") (pintype "bidirectional"))
    )
    (net (code "80") (name "/ddr1_dq4") (class "Default")
      (node (ref "D4") (pin "D17") (pinfunction "IO,_(DIFFIO_RX_T35n,_DIFFOUT_T35n,_DQ5T,__,_T_DQ_4,_T_DQ_4)_D17") (pintype "bidirectional"))
    )
    (net (code "81") (name "/ddr1_dq5") (class "Default")
      (node (ref "D4") (pin "E17") (pinfunction "IO,_(DIFFIO_RX_T35p,_DIFFOUT_T35p,_DQ5T,__,_T_DQ_5,_T_DQ_5)_E17") (pintype "bidirectional"))
    )
    (net (code "82") (name "/ddr1_dq6") (class "Default")
      (node (ref "D4") (pin "D12") (pinfunction "IO,_(DIFFIO_TX_T36p,_DIFFOUT_T36p,_DQ5T,__,_T_DQ_6,_T_DQ_6)_D12") (pintype "bidirectional"))
    )
    (net (code "83") (name "/ddr1_dq7") (class "Default")
      (node (ref "D4") (pin "A14") (pinfunction "IO,_(DIFFIO_TX_T34n,_DIFFOUT_T34n,_DQ5T,__,_T_DQ_7,_T_DQ_7)_A14") (pintype "bidirectional"))
    )
    (net (code "84") (name "/ddr1_dq8") (class "Default")
      (node (ref "D4") (pin "B17") (pinfunction "IO,_(DIFFIO_RX_T31n,_DIFFOUT_T31n,_DQ4T,_DQ2T,_T_DQ_8,_T_DQ_8)_B17") (pintype "bidirectional"))
    )
    (net (code "85") (name "/ddr1_dq9") (class "Default")
      (node (ref "D4") (pin "C17") (pinfunction "IO,_(DIFFIO_RX_T31p,_DIFFOUT_T31p,_DQ4T,_DQ2T,_T_DQ_9,_T_DQ_9)_C17") (pintype "bidirectional"))
    )
    (net (code "86") (name "/ddr1_dq10") (class "Default")
      (node (ref "D4") (pin "A16") (pinfunction "IO,_(DIFFIO_TX_T32p,_DIFFOUT_T32p,_DQ4T,_DQ2T,_T_DQ_10,_T_DQ_10)_A16") (pintype "bidirectional"))
    )
    (net (code "87") (name "/ddr1_dq11") (class "Default")
      (node (ref "D4") (pin "C14") (pinfunction "IO,_(DIFFIO_TX_T30n,_DIFFOUT_T30n,_DQ4T,_DQ2T,_T_DQ_11,_T_DQ_11)_C14") (pintype "bidirectional"))
    )
    (net (code "88") (name "/ddr1_dq12") (class "Default")
      (node (ref "D4") (pin "F18") (pinfunction "IO,_(DIFFIO_RX_T27n,_DIFFOUT_T27n,_DQ4T,_DQ2T,_T_DQ_12,_T_DQ_12)_F18") (pintype "bidirectional"))
    )
    (net (code "89") (name "/ddr1_dq13") (class "Default")
      (node (ref "D4") (pin "G18") (pinfunction "IO,_(DIFFIO_RX_T27p,_DIFFOUT_T27p,_DQ4T,_DQ2T,_T_DQ_13,_T_DQ_13)_G18") (pintype "bidirectional"))
    )
    (net (code "90") (name "/ddr1_dq14") (class "Default")
      (node (ref "D4") (pin "B18") (pinfunction "IO,_(DIFFIO_TX_T28p,_DIFFOUT_T28p,_DQ4T,_DQ2T,_T_DQ_14,_T_DQ_14)_B18") (pintype "bidirectional"))
    )
    (net (code "91") (name "/ddr1_dq15") (class "Default")
      (node (ref "D4") (pin "A19") (pinfunction "IO,_(DIFFIO_TX_T26n,_DIFFOUT_T26n,_DQ4T,_DQ2T,_T_DQ_15,_T_DQ_15)_A19") (pintype "bidirectional"))
    )
    (net (code "92") (name "/ddr1_dqs0_n") (class "Default")
      (node (ref "D4") (pin "J17") (pinfunction "IO,_(DIFFIO_RX_T37n,_DIFFOUT_T37n,_DQSn5T,__,_T_DQS#_0,_T_DQS#_0)_J17") (pintype "bidirectional"))
    )
    (net (code "93") (name "/ddr1_dqs0_p") (class "Default")
      (node (ref "D4") (pin "K17") (pinfunction "IO,_(DIFFIO_RX_T37p,_DIFFOUT_T37p,_DQS5T,__,_T_DQS_0,_T_DQS_0)_K17") (pintype "bidirectional"))
    )
    (net (code "94") (name "/ddr1_dqs1_n") (class "Default")
      (node (ref "D4") (pin "L16") (pinfunction "IO,_(DIFFIO_RX_T29n,_DIFFOUT_T29n,_DQSn4T,_DQ2T,_T_DQS#_1,_T_DQS#_1)_L16") (pintype "bidirectional"))
    )
    (net (code "95") (name "/ddr1_dqs1_p") (class "Default")
      (node (ref "D4") (pin "K16") (pinfunction "IO,_(DIFFIO_RX_T29p,_DIFFOUT_T29p,_DQS4T,_DQ2T,_T_DQS_1,_T_DQS_1)_K16") (pintype "bidirectional"))
    )
    (net (code "96") (name "/ddr1_odt") (class "Default")
      (node (ref "D4") (pin "B13") (pinfunction "IO,_(DIFFIO_TX_T38p,_DIFFOUT_T38p,__,__,_T_ODT_0,_T_ODT_0)_B13") (pintype "bidirectional"))
    )
    (net (code "97") (name "/ddr1_ras") (class "Default")
      (node (ref "D4") (pin "B8") (pinfunction "IO,_(DIFFIO_TX_T50n,_DIFFOUT_T50n,_DQ7T,__,_T_RAS#)_B8") (pintype "bidirectional"))
    )
    (net (code "98") (name "/ddr1_reset_n") (class "Default")
      (node (ref "D4") (pin "B22") (pinfunction "IO,_(DIFFIO_TX_T22p,_DIFFOUT_T22p,__,__,_T_RESET#,_T_RESET#)_B22") (pintype "bidirectional"))
    )
    (net (code "99") (name "/ddr1_we") (class "Default")
      (node (ref "D4") (pin "C7") (pinfunction "IO,_(DIFFIO_TX_T56p,_DIFFOUT_T56p,_DQ7T,__,_T_WE#)_C7") (pintype "bidirectional"))
    )
    (net (code "100") (name "Net-(D4C-IO,_RZQ_0,_(DIFFIO_TX_B41n,_DIFFOUT_B41n))") (class "Default")
      (node (ref "D4") (pin "AK13") (pinfunction "IO,_RZQ_0,_(DIFFIO_TX_B41n,_DIFFOUT_B41n)_AK13") (pintype "bidirectional"))
      (node (ref "R24") (pin "1") (pinfunction "1_1") (pintype "passive"))
    )
    (net (code "101") (name "Net-(D4G-IO,_RZQ_2,_(DIFFIO_TX_T40n,_DIFFOUT_T40n))") (class "Default")
      (node (ref "D4") (pin "B12") (pinfunction "IO,_RZQ_2,_(DIFFIO_TX_T40n,_DIFFOUT_T40n)_B12") (pintype "bidirectional"))
      (node (ref "R23") (pin "1") (pinfunction "1_1") (pintype "passive"))
    )
    (net (code "102") (name "unconnected-(D4B-IO,_(DIFFIO_RX_B18n,_DIFFOUT_B18n,_DQ3B,_DQ1B)-PadAD13)") (class "Default")
      (node (ref "D4") (pin "AD13") (pinfunction "IO,_(DIFFIO_RX_B18n,_DIFFOUT_B18n,_DQ3B,_DQ1B)_AD13") (pintype "bidirectional"))
    )
    (net (code "103") (name "unconnected-(D4B-IO,_(DIFFIO_RX_B18p,_DIFFOUT_B18p,_DQ3B,_DQ1B)-PadAD12)") (class "Default")
      (node (ref "D4") (pin "AD12") (pinfunction "IO,_(DIFFIO_RX_B18p,_DIFFOUT_B18p,_DQ3B,_DQ1B)_AD12") (pintype "bidirectional"))
    )
    (net (code "104") (name "unconnected-(D4B-IO,_(DIFFIO_RX_B19n,_DIFFOUT_B19n,_DQSn3B,_DQ1B)-PadW12)") (class "Default")
      (node (ref "D4") (pin "W12") (pinfunction "IO,_(DIFFIO_RX_B19n,_DIFFOUT_B19n,_DQSn3B,_DQ1B)_W12") (pintype "bidirectional"))
    )
    (net (code "105") (name "unconnected-(D4B-IO,_(DIFFIO_RX_B19p,_DIFFOUT_B19p,_DQS3B,_DQ1B)-PadV12)") (class "Default")
      (node (ref "D4") (pin "V12") (pinfunction "IO,_(DIFFIO_RX_B19p,_DIFFOUT_B19p,_DQS3B,_DQ1B)_V12") (pintype "bidirectional"))
    )
    (net (code "106") (name "unconnected-(D4B-IO,_(DIFFIO_RX_B22n,_DIFFOUT_B22n,_DQ3B,_DQ1B)-PadAE13)") (class "Default")
      (node (ref "D4") (pin "AE13") (pinfunction "IO,_(DIFFIO_RX_B22n,_DIFFOUT_B22n,_DQ3B,_DQ1B)_AE13") (pintype "bidirectional"))
    )
    (net (code "107") (name "unconnected-(D4B-IO,_(DIFFIO_RX_B22p,_DIFFOUT_B22p,_DQ3B,_DQ1B)-PadAE12)") (class "Default")
      (node (ref "D4") (pin "AE12") (pinfunction "IO,_(DIFFIO_RX_B22p,_DIFFOUT_B22p,_DQ3B,_DQ1B)_AE12") (pintype "bidirectional"))
    )
    (net (code "108") (name "unconnected-(D4B-IO,_(DIFFIO_RX_B23n,_DIFFOUT_B23n)-PadAB13)") (class "Default")
      (node (ref "D4") (pin "AB13") (pinfunction "IO,_(DIFFIO_RX_B23n,_DIFFOUT_B23n)_AB13") (pintype "bidirectional"))
    )
    (net (code "109") (name "unconnected-(D4B-IO,_(DIFFIO_RX_B23p,_DIFFOUT_B23p)-PadAB12)") (class "Default")
      (node (ref "D4") (pin "AB12") (pinfunction "IO,_(DIFFIO_RX_B23p,_DIFFOUT_B23p)_AB12") (pintype "bidirectional"))
    )
    (net (code "110") (name "unconnected-(D4B-IO,_(DIFFIO_RX_B26n,_DIFFOUT_B26n,_DQ4B,_DQ1B,_B_A_15)-PadAG12)") (class "Default")
      (node (ref "D4") (pin "AG12") (pinfunction "IO,_(DIFFIO_RX_B26n,_DIFFOUT_B26n,_DQ4B,_DQ1B,_B_A_15)_AG12") (pintype "bidirectional"))
    )
    (net (code "111") (name "unconnected-(D4B-IO,_(DIFFIO_RX_B27n,_DIFFOUT_B27n,_DQSn4B,_DQSn1B,_B_CS#_1,_B_CS#_1)-PadAA13)") (class "Default")
      (node (ref "D4") (pin "AA13") (pinfunction "IO,_(DIFFIO_RX_B27n,_DIFFOUT_B27n,_DQSn4B,_DQSn1B,_B_CS#_1,_B_CS#_1)_AA13") (pintype "bidirectional"))
    )
    (net (code "112") (name "unconnected-(D4B-IO,_(DIFFIO_TX_B17n,_DIFFOUT_B17n)-PadAF10)") (class "Default")
      (node (ref "D4") (pin "AF10") (pinfunction "IO,_(DIFFIO_TX_B17n,_DIFFOUT_B17n)_AF10") (pintype "bidirectional"))
    )
    (net (code "113") (name "unconnected-(D4B-IO,_(DIFFIO_TX_B17p,_DIFFOUT_B17p,_DQ3B,_DQ1B)-PadAE10)") (class "Default")
      (node (ref "D4") (pin "AE10") (pinfunction "IO,_(DIFFIO_TX_B17p,_DIFFOUT_B17p,_DQ3B,_DQ1B)_AE10") (pintype "bidirectional"))
    )
    (net (code "114") (name "unconnected-(D4B-IO,_(DIFFIO_TX_B20n,_DIFFOUT_B20n,_DQ3B,_DQ1B)-PadAJ2)") (class "Default")
      (node (ref "D4") (pin "AJ2") (pinfunction "IO,_(DIFFIO_TX_B20n,_DIFFOUT_B20n,_DQ3B,_DQ1B)_AJ2") (pintype "bidirectional"))
    )
    (net (code "115") (name "unconnected-(D4B-IO,_(DIFFIO_TX_B20p,_DIFFOUT_B20p)-PadAJ1)") (class "Default")
      (node (ref "D4") (pin "AJ1") (pinfunction "IO,_(DIFFIO_TX_B20p,_DIFFOUT_B20p)_AJ1") (pintype "bidirectional"))
    )
    (net (code "116") (name "unconnected-(D4B-IO,_(DIFFIO_TX_B21n,_DIFFOUT_B21n,_DQ3B,_DQ1B)-PadAK3)") (class "Default")
      (node (ref "D4") (pin "AK3") (pinfunction "IO,_(DIFFIO_TX_B21n,_DIFFOUT_B21n,_DQ3B,_DQ1B)_AK3") (pintype "bidirectional"))
    )
    (net (code "117") (name "unconnected-(D4B-IO,_(DIFFIO_TX_B21p,_DIFFOUT_B21p,_DQ3B,_DQ1B)-PadAJ3)") (class "Default")
      (node (ref "D4") (pin "AJ3") (pinfunction "IO,_(DIFFIO_TX_B21p,_DIFFOUT_B21p,_DQ3B,_DQ1B)_AJ3") (pintype "bidirectional"))
    )
    (net (code "118") (name "unconnected-(D4B-IO,_(DIFFIO_TX_B24n,_DIFFOUT_B24n,_DQ3B,_DQ1B)-PadAJ5)") (class "Default")
      (node (ref "D4") (pin "AJ5") (pinfunction "IO,_(DIFFIO_TX_B24n,_DIFFOUT_B24n,_DQ3B,_DQ1B)_AJ5") (pintype "bidirectional"))
    )
    (net (code "119") (name "unconnected-(D4B-IO,_(DIFFIO_TX_B24p,_DIFFOUT_B24p,_DQ3B,_DQ1B)-PadAJ4)") (class "Default")
      (node (ref "D4") (pin "AJ4") (pinfunction "IO,_(DIFFIO_TX_B24p,_DIFFOUT_B24p,_DQ3B,_DQ1B)_AJ4") (pintype "bidirectional"))
    )
    (net (code "120") (name "unconnected-(D4B-IO,_CLK0n,_FPLL_BL_FBn,_(DIFFIO_RX_B31n,_DIFFOUT_B31n)-PadAC14)") (class "Default")
      (node (ref "D4") (pin "AC14") (pinfunction "IO,_CLK0n,_FPLL_BL_FBn,_(DIFFIO_RX_B31n,_DIFFOUT_B31n)_AC14") (pintype "bidirectional"))
    )
    (net (code "121") (name "unconnected-(D4B-IO,_CLK0p,_FPLL_BL_FBp,_(DIFFIO_RX_B31p,_DIFFOUT_B31p)-PadAB14)") (class "Default")
      (node (ref "D4") (pin "AB14") (pinfunction "IO,_CLK0p,_FPLL_BL_FBp,_(DIFFIO_RX_B31p,_DIFFOUT_B31p)_AB14") (pintype "bidirectional"))
    )
    (net (code "122") (name "unconnected-(D4B-IO,_CLK1n,_(DIFFIO_RX_B39n,_DIFFOUT_B39n)-PadAA15)") (class "Default")
      (node (ref "D4") (pin "AA15") (pinfunction "IO,_CLK1n,_(DIFFIO_RX_B39n,_DIFFOUT_B39n)_AA15") (pintype "bidirectional"))
    )
    (net (code "123") (name "unconnected-(D4B-IO,_CLK1p,_(DIFFIO_RX_B39p,_DIFFOUT_B39p)-PadY15)") (class "Default")
      (node (ref "D4") (pin "Y15") (pinfunction "IO,_CLK1p,_(DIFFIO_RX_B39p,_DIFFOUT_B39p)_Y15") (pintype "bidirectional"))
    )
    (net (code "124") (name "unconnected-(D4C-IO,_(DIFFIO_RX_B58n,_DIFFOUT_B58n,_DQ8B,_DQ2B,_B_DQ_16,_B_DQ_16)-PadAE18)") (class "Default")
      (node (ref "D4") (pin "AE18") (pinfunction "IO,_(DIFFIO_RX_B58n,_DIFFOUT_B58n,_DQ8B,_DQ2B,_B_DQ_16,_B_DQ_16)_AE18") (pintype "bidirectional"))
    )
    (net (code "125") (name "unconnected-(D4C-IO,_(DIFFIO_RX_B58p,_DIFFOUT_B58p,_DQ8B,_DQ2B,_B_DQ_17,_B_DQ_17)-PadAD18)") (class "Default")
      (node (ref "D4") (pin "AD18") (pinfunction "IO,_(DIFFIO_RX_B58p,_DIFFOUT_B58p,_DQ8B,_DQ2B,_B_DQ_17,_B_DQ_17)_AD18") (pintype "bidirectional"))
    )
    (net (code "126") (name "unconnected-(D4C-IO,_(DIFFIO_RX_B59n,_DIFFOUT_B59n,_DQSn8B,_DQSn2B,_B_DQS#_2,_B_DQS#_2)-PadAA20)") (class "Default")
      (node (ref "D4") (pin "AA20") (pinfunction "IO,_(DIFFIO_RX_B59n,_DIFFOUT_B59n,_DQSn8B,_DQSn2B,_B_DQS#_2,_B_DQS#_2)_AA20") (pintype "bidirectional"))
    )
    (net (code "127") (name "unconnected-(D4C-IO,_(DIFFIO_RX_B59p,_DIFFOUT_B59p,_DQS8B,_DQS2B,_B_DQS_2,_B_DQS_2)-PadY20)") (class "Default")
      (node (ref "D4") (pin "Y20") (pinfunction "IO,_(DIFFIO_RX_B59p,_DIFFOUT_B59p,_DQS8B,_DQS2B,_B_DQS_2,_B_DQS_2)_Y20") (pintype "bidirectional"))
    )
    (net (code "128") (name "unconnected-(D4C-IO,_(DIFFIO_RX_B62n,_DIFFOUT_B62n,_DQ8B,_DQ2B,_B_DQ_20,_B_DQ_20)-PadAF19)") (class "Default")
      (node (ref "D4") (pin "AF19") (pinfunction "IO,_(DIFFIO_RX_B62n,_DIFFOUT_B62n,_DQ8B,_DQ2B,_B_DQ_20,_B_DQ_20)_AF19") (pintype "bidirectional"))
    )
    (net (code "129") (name "unconnected-(D4C-IO,_(DIFFIO_RX_B62p,_DIFFOUT_B62p,_DQ8B,_DQ2B,_B_DQ_21,_B_DQ_21)-PadAF18)") (class "Default")
      (node (ref "D4") (pin "AF18") (pinfunction "IO,_(DIFFIO_RX_B62p,_DIFFOUT_B62p,_DQ8B,_DQ2B,_B_DQ_21,_B_DQ_21)_AF18") (pintype "bidirectional"))
    )
    (net (code "130") (name "unconnected-(D4C-IO,_(DIFFIO_RX_B66n,_DIFFOUT_B66n,_DQ9B,_DQ3B,_B_DQ_24,_B_DQ_24)-PadAG19)") (class "Default")
      (node (ref "D4") (pin "AG19") (pinfunction "IO,_(DIFFIO_RX_B66n,_DIFFOUT_B66n,_DQ9B,_DQ3B,_B_DQ_24,_B_DQ_24)_AG19") (pintype "bidirectional"))
    )
    (net (code "131") (name "unconnected-(D4C-IO,_(DIFFIO_RX_B66p,_DIFFOUT_B66p,_DQ9B,_DQ3B,_B_DQ_25,_B_DQ_25)-PadAG18)") (class "Default")
      (node (ref "D4") (pin "AG18") (pinfunction "IO,_(DIFFIO_RX_B66p,_DIFFOUT_B66p,_DQ9B,_DQ3B,_B_DQ_25,_B_DQ_25)_AG18") (pintype "bidirectional"))
    )
    (net (code "132") (name "unconnected-(D4C-IO,_(DIFFIO_RX_B67n,_DIFFOUT_B67n,_DQSn9B,_DQ3B,_B_DQS#_3,_B_DQS#_3)-PadAC19)") (class "Default")
      (node (ref "D4") (pin "AC19") (pinfunction "IO,_(DIFFIO_RX_B67n,_DIFFOUT_B67n,_DQSn9B,_DQ3B,_B_DQS#_3,_B_DQS#_3)_AC19") (pintype "bidirectional"))
    )
    (net (code "133") (name "unconnected-(D4C-IO,_(DIFFIO_RX_B67p,_DIFFOUT_B67p,_DQS9B,_DQ3B,_B_DQS_3,_B_DQS_3)-PadAB19)") (class "Default")
      (node (ref "D4") (pin "AB19") (pinfunction "IO,_(DIFFIO_RX_B67p,_DIFFOUT_B67p,_DQS9B,_DQ3B,_B_DQS_3,_B_DQS_3)_AB19") (pintype "bidirectional"))
    )
    (net (code "134") (name "unconnected-(D4C-IO,_(DIFFIO_RX_B70n,_DIFFOUT_B70n,_DQ9B,_DQ3B,_B_DQ_28,_B_DQ_28)-PadAE20)") (class "Default")
      (node (ref "D4") (pin "AE20") (pinfunction "IO,_(DIFFIO_RX_B70n,_DIFFOUT_B70n,_DQ9B,_DQ3B,_B_DQ_28,_B_DQ_28)_AE20") (pintype "bidirectional"))
    )
    (net (code "135") (name "unconnected-(D4C-IO,_(DIFFIO_RX_B70p,_DIFFOUT_B70p,_DQ9B,_DQ3B,_B_DQ_29,_B_DQ_29)-PadAD19)") (class "Default")
      (node (ref "D4") (pin "AD19") (pinfunction "IO,_(DIFFIO_RX_B70p,_DIFFOUT_B70p,_DQ9B,_DQ3B,_B_DQ_29,_B_DQ_29)_AD19") (pintype "bidirectional"))
    )
    (net (code "136") (name "unconnected-(D4C-IO,_(DIFFIO_RX_B74n,_DIFFOUT_B74n,_DQ10B,_DQ3B,_B_DQ_32,_B_DQ_32)-PadAG21)") (class "Default")
      (node (ref "D4") (pin "AG21") (pinfunction "IO,_(DIFFIO_RX_B74n,_DIFFOUT_B74n,_DQ10B,_DQ3B,_B_DQ_32,_B_DQ_32)_AG21") (pintype "bidirectional"))
    )
    (net (code "137") (name "unconnected-(D4C-IO,_(DIFFIO_RX_B74p,_DIFFOUT_B74p,_DQ10B,_DQ3B,_B_DQ_33,_B_DQ_33)-PadAF20)") (class "Default")
      (node (ref "D4") (pin "AF20") (pinfunction "IO,_(DIFFIO_RX_B74p,_DIFFOUT_B74p,_DQ10B,_DQ3B,_B_DQ_33,_B_DQ_33)_AF20") (pintype "bidirectional"))
    )
    (net (code "138") (name "unconnected-(D4C-IO,_(DIFFIO_RX_B75n,_DIFFOUT_B75n,_DQSn10B,_DQSn3B,_B_DQS#_4,_B_DQS#_4)-PadAD20)") (class "Default")
      (node (ref "D4") (pin "AD20") (pinfunction "IO,_(DIFFIO_RX_B75n,_DIFFOUT_B75n,_DQSn10B,_DQSn3B,_B_DQS#_4,_B_DQS#_4)_AD20") (pintype "bidirectional"))
    )
    (net (code "139") (name "unconnected-(D4C-IO,_(DIFFIO_RX_B75p,_DIFFOUT_B75p,_DQS10B,_DQS3B,_B_DQS_4,_B_DQS_4)-PadAC21)") (class "Default")
      (node (ref "D4") (pin "AC21") (pinfunction "IO,_(DIFFIO_RX_B75p,_DIFFOUT_B75p,_DQS10B,_DQS3B,_B_DQS_4,_B_DQS_4)_AC21") (pintype "bidirectional"))
    )
    (net (code "140") (name "unconnected-(D4C-IO,_(DIFFIO_RX_B78n,_DIFFOUT_B78n,_DQ10B,_DQ3B,_B_DQ_36,_B_DQ_36)-PadAG22)") (class "Default")
      (node (ref "D4") (pin "AG22") (pinfunction "IO,_(DIFFIO_RX_B78n,_DIFFOUT_B78n,_DQ10B,_DQ3B,_B_DQ_36,_B_DQ_36)_AG22") (pintype "bidirectional"))
    )
    (net (code "141") (name "unconnected-(D4C-IO,_(DIFFIO_RX_B78p,_DIFFOUT_B78p,_DQ10B,_DQ3B,_B_DQ_37,_B_DQ_37)-PadAF21)") (class "Default")
      (node (ref "D4") (pin "AF21") (pinfunction "IO,_(DIFFIO_RX_B78p,_DIFFOUT_B78p,_DQ10B,_DQ3B,_B_DQ_37,_B_DQ_37)_AF21") (pintype "bidirectional"))
    )
    (net (code "142") (name "unconnected-(D4C-IO,_(DIFFIO_TX_B45n,_DIFFOUT_B45n,_DQ6B,__,_B_ODT_1,_B_ODT_1)-PadAK15)") (class "Default")
      (node (ref "D4") (pin "AK15") (pinfunction "IO,_(DIFFIO_TX_B45n,_DIFFOUT_B45n,_DQ6B,__,_B_ODT_1,_B_ODT_1)_AK15") (pintype "bidirectional"))
    )
    (net (code "143") (name "unconnected-(D4C-IO,_(DIFFIO_TX_B52p,_DIFFOUT_B52p,__,__,_B_CKE_1,_B_CKE_1)-PadAJ17)") (class "Default")
      (node (ref "D4") (pin "AJ17") (pinfunction "IO,_(DIFFIO_TX_B52p,_DIFFOUT_B52p,__,__,_B_CKE_1,_B_CKE_1)_AJ17") (pintype "bidirectional"))
    )
    (net (code "144") (name "unconnected-(D4C-IO,_(DIFFIO_TX_B57p,_DIFFOUT_B57p,_DQ8B,_DQ2B,_B_DQ_18,_B_DQ_18)-PadAJ20)") (class "Default")
      (node (ref "D4") (pin "AJ20") (pinfunction "IO,_(DIFFIO_TX_B57p,_DIFFOUT_B57p,_DQ8B,_DQ2B,_B_DQ_18,_B_DQ_18)_AJ20") (pintype "bidirectional"))
    )
    (net (code "145") (name "unconnected-(D4C-IO,_(DIFFIO_TX_B60n,_DIFFOUT_B60n,_DQ8B,_DQ2B,_B_DQ_19,_B_DQ_19)-PadAK22)") (class "Default")
      (node (ref "D4") (pin "AK22") (pinfunction "IO,_(DIFFIO_TX_B60n,_DIFFOUT_B60n,_DQ8B,_DQ2B,_B_DQ_19,_B_DQ_19)_AK22") (pintype "bidirectional"))
    )
    (net (code "146") (name "unconnected-(D4C-IO,_(DIFFIO_TX_B61p,_DIFFOUT_B61p,_DQ8B,_DQ2B,_B_DQ_22,_B_DQ_22)-PadAH21)") (class "Default")
      (node (ref "D4") (pin "AH21") (pinfunction "IO,_(DIFFIO_TX_B61p,_DIFFOUT_B61p,_DQ8B,_DQ2B,_B_DQ_22,_B_DQ_22)_AH21") (pintype "bidirectional"))
    )
    (net (code "147") (name "unconnected-(D4C-IO,_(DIFFIO_TX_B64n,_DIFFOUT_B64n,_DQ8B,_DQ2B,_B_DQ_23,_B_DQ_23)-PadAK23)") (class "Default")
      (node (ref "D4") (pin "AK23") (pinfunction "IO,_(DIFFIO_TX_B64n,_DIFFOUT_B64n,_DQ8B,_DQ2B,_B_DQ_23,_B_DQ_23)_AK23") (pintype "bidirectional"))
    )
    (net (code "148") (name "unconnected-(D4C-IO,_(DIFFIO_TX_B64p,_DIFFOUT_B64p,_DQ8B,_DQ2B,_B_DM_2,_B_DM_2)-PadAJ23)") (class "Default")
      (node (ref "D4") (pin "AJ23") (pinfunction "IO,_(DIFFIO_TX_B64p,_DIFFOUT_B64p,_DQ8B,_DQ2B,_B_DM_2,_B_DM_2)_AJ23") (pintype "bidirectional"))
    )
    (net (code "149") (name "unconnected-(D4C-IO,_(DIFFIO_TX_B65p,_DIFFOUT_B65p,_DQ9B,_DQ3B,_B_DQ_26,_B_DQ_26)-PadAH24)") (class "Default")
      (node (ref "D4") (pin "AH24") (pinfunction "IO,_(DIFFIO_TX_B65p,_DIFFOUT_B65p,_DQ9B,_DQ3B,_B_DQ_26,_B_DQ_26)_AH24") (pintype "bidirectional"))
    )
    (net (code "150") (name "unconnected-(D4C-IO,_(DIFFIO_TX_B68n,_DIFFOUT_B68n,_DQ9B,_DQ3B,_B_DQ_27,_B_DQ_27)-PadAK25)") (class "Default")
      (node (ref "D4") (pin "AK25") (pinfunction "IO,_(DIFFIO_TX_B68n,_DIFFOUT_B68n,_DQ9B,_DQ3B,_B_DQ_27,_B_DQ_27)_AK25") (pintype "bidirectional"))
    )
    (net (code "151") (name "unconnected-(D4C-IO,_(DIFFIO_TX_B69p,_DIFFOUT_B69p,_DQ9B,_DQ3B,_B_DQ_30,_B_DQ_30)-PadAG24)") (class "Default")
      (node (ref "D4") (pin "AG24") (pinfunction "IO,_(DIFFIO_TX_B69p,_DIFFOUT_B69p,_DQ9B,_DQ3B,_B_DQ_30,_B_DQ_30)_AG24") (pintype "bidirectional"))
    )
    (net (code "152") (name "unconnected-(D4C-IO,_(DIFFIO_TX_B72n,_DIFFOUT_B72n,_DQ9B,_DQ3B,_B_DQ_31,_B_DQ_31)-PadAK26)") (class "Default")
      (node (ref "D4") (pin "AK26") (pinfunction "IO,_(DIFFIO_TX_B72n,_DIFFOUT_B72n,_DQ9B,_DQ3B,_B_DQ_31,_B_DQ_31)_AK26") (pintype "bidirectional"))
    )
    (net (code "153") (name "unconnected-(D4C-IO,_(DIFFIO_TX_B72p,_DIFFOUT_B72p,_DQ9B,_DQ3B,_B_DM_3,_B_DM_3)-PadAJ27)") (class "Default")
      (node (ref "D4") (pin "AJ27") (pinfunction "IO,_(DIFFIO_TX_B72p,_DIFFOUT_B72p,_DQ9B,_DQ3B,_B_DM_3,_B_DM_3)_AJ27") (pintype "bidirectional"))
    )
    (net (code "154") (name "unconnected-(D4C-IO,_(DIFFIO_TX_B73p,_DIFFOUT_B73p,_DQ10B,_DQ3B,_B_DQ_34,_B_DQ_34)-PadAK27)") (class "Default")
      (node (ref "D4") (pin "AK27") (pinfunction "IO,_(DIFFIO_TX_B73p,_DIFFOUT_B73p,_DQ10B,_DQ3B,_B_DQ_34,_B_DQ_34)_AK27") (pintype "bidirectional"))
    )
    (net (code "155") (name "unconnected-(D4C-IO,_(DIFFIO_TX_B76n,_DIFFOUT_B76n,_DQ10B,_DQ3B,_B_DQ_35,_B_DQ_35)-PadAH26)") (class "Default")
      (node (ref "D4") (pin "AH26") (pinfunction "IO,_(DIFFIO_TX_B76n,_DIFFOUT_B76n,_DQ10B,_DQ3B,_B_DQ_35,_B_DQ_35)_AH26") (pintype "bidirectional"))
    )
    (net (code "156") (name "unconnected-(D4C-IO,_(DIFFIO_TX_B77p,_DIFFOUT_B77p,_DQ10B,_DQ3B,_B_DQ_38,_B_DQ_38)-PadAE22)") (class "Default")
      (node (ref "D4") (pin "AE22") (pinfunction "IO,_(DIFFIO_TX_B77p,_DIFFOUT_B77p,_DQ10B,_DQ3B,_B_DQ_38,_B_DQ_38)_AE22") (pintype "bidirectional"))
    )
    (net (code "157") (name "unconnected-(D4C-IO,_(DIFFIO_TX_B80n,_DIFFOUT_B80n,_DQ10B,_DQ3B,_B_DQ_39,_B_DQ_39)-PadAH22)") (class "Default")
      (node (ref "D4") (pin "AH22") (pinfunction "IO,_(DIFFIO_TX_B80n,_DIFFOUT_B80n,_DQ10B,_DQ3B,_B_DQ_39,_B_DQ_39)_AH22") (pintype "bidirectional"))
    )
    (net (code "158") (name "unconnected-(D4C-IO,_(DIFFIO_TX_B80p,_DIFFOUT_B80p,_DQ10B,_DQ3B,_B_DM_4,_B_DM_4)-PadAG23)") (class "Default")
      (node (ref "D4") (pin "AG23") (pinfunction "IO,_(DIFFIO_TX_B80p,_DIFFOUT_B80p,_DQ10B,_DQ3B,_B_DM_4,_B_DM_4)_AG23") (pintype "bidirectional"))
    )
    (net (code "159") (name "unconnected-(D4C-IO,_CLK2n,_(DIFFIO_RX_B47n,_DIFFOUT_B47n)-PadAC15)") (class "Default")
      (node (ref "D4") (pin "AC15") (pinfunction "IO,_CLK2n,_(DIFFIO_RX_B47n,_DIFFOUT_B47n)_AC15") (pintype "bidirectional"))
    )
    (net (code "160") (name "unconnected-(D4C-IO,_CLK2p,_(DIFFIO_RX_B47p,_DIFFOUT_B47p)-PadAB16)") (class "Default")
      (node (ref "D4") (pin "AB16") (pinfunction "IO,_CLK2p,_(DIFFIO_RX_B47p,_DIFFOUT_B47p)_AB16") (pintype "bidirectional"))
    )
    (net (code "161") (name "unconnected-(D4C-IO,_CLK3n,_(DIFFIO_RX_B55n,_DIFFOUT_B55n)-PadAB18)") (class "Default")
      (node (ref "D4") (pin "AB18") (pinfunction "IO,_CLK3n,_(DIFFIO_RX_B55n,_DIFFOUT_B55n)_AB18") (pintype "bidirectional"))
    )
    (net (code "162") (name "unconnected-(D4C-IO,_CLK3p,_(DIFFIO_RX_B55p,_DIFFOUT_B55p)-PadAB17)") (class "Default")
      (node (ref "D4") (pin "AB17") (pinfunction "IO,_CLK3p,_(DIFFIO_RX_B55p,_DIFFOUT_B55p)_AB17") (pintype "bidirectional"))
    )
    (net (code "163") (name "unconnected-(D4G-IO,_(DIFFIO_RX_T3n,_DIFFOUT_T3n,_DQ1T,_DQ1T,_T_DQ_36,_T_DQ_36)-PadG23)") (class "Default")
      (node (ref "D4") (pin "G23") (pinfunction "IO,_(DIFFIO_RX_T3n,_DIFFOUT_T3n,_DQ1T,_DQ1T,_T_DQ_36,_T_DQ_36)_G23") (pintype "bidirectional"))
    )
    (net (code "164") (name "unconnected-(D4G-IO,_(DIFFIO_RX_T3p,_DIFFOUT_T3p,_DQ1T,_DQ1T,_T_DQ_37,_T_DQ_37)-PadG22)") (class "Default")
      (node (ref "D4") (pin "G22") (pinfunction "IO,_(DIFFIO_RX_T3p,_DIFFOUT_T3p,_DQ1T,_DQ1T,_T_DQ_37,_T_DQ_37)_G22") (pintype "bidirectional"))
    )
    (net (code "165") (name "unconnected-(D4G-IO,_(DIFFIO_RX_T5n,_DIFFOUT_T5n,_DQSn1T,_DQSn1T,_T_DQS#_4,_T_DQS#_4)-PadL19)") (class "Default")
      (node (ref "D4") (pin "L19") (pinfunction "IO,_(DIFFIO_RX_T5n,_DIFFOUT_T5n,_DQSn1T,_DQSn1T,_T_DQS#_4,_T_DQS#_4)_L19") (pintype "bidirectional"))
    )
    (net (code "166") (name "unconnected-(D4G-IO,_(DIFFIO_RX_T5p,_DIFFOUT_T5p,_DQS1T,_DQS1T,_T_DQS_4,_T_DQS_4)-PadL20)") (class "Default")
      (node (ref "D4") (pin "L20") (pinfunction "IO,_(DIFFIO_RX_T5p,_DIFFOUT_T5p,_DQS1T,_DQS1T,_T_DQS_4,_T_DQS_4)_L20") (pintype "bidirectional"))
    )
    (net (code "167") (name "unconnected-(D4G-IO,_(DIFFIO_RX_T7n,_DIFFOUT_T7n,_DQ1T,_DQ1T,_T_DQ_32,_T_DQ_32)-PadE21)") (class "Default")
      (node (ref "D4") (pin "E21") (pinfunction "IO,_(DIFFIO_RX_T7n,_DIFFOUT_T7n,_DQ1T,_DQ1T,_T_DQ_32,_T_DQ_32)_E21") (pintype "bidirectional"))
    )
    (net (code "168") (name "unconnected-(D4G-IO,_(DIFFIO_RX_T7p,_DIFFOUT_T7p,_DQ1T,_DQ1T,_T_DQ_33,_T_DQ_33)-PadE22)") (class "Default")
      (node (ref "D4") (pin "E22") (pinfunction "IO,_(DIFFIO_RX_T7p,_DIFFOUT_T7p,_DQ1T,_DQ1T,_T_DQ_33,_T_DQ_33)_E22") (pintype "bidirectional"))
    )
    (net (code "169") (name "unconnected-(D4G-IO,_(DIFFIO_RX_T11n,_DIFFOUT_T11n,_DQ2T,_DQ1T,_T_DQ_28,_T_DQ_28)-PadC20)") (class "Default")
      (node (ref "D4") (pin "C20") (pinfunction "IO,_(DIFFIO_RX_T11n,_DIFFOUT_T11n,_DQ2T,_DQ1T,_T_DQ_28,_T_DQ_28)_C20") (pintype "bidirectional"))
    )
    (net (code "170") (name "unconnected-(D4G-IO,_(DIFFIO_RX_T11p,_DIFFOUT_T11p,_DQ2T,_DQ1T,_T_DQ_29,_T_DQ_29)-PadC21)") (class "Default")
      (node (ref "D4") (pin "C21") (pinfunction "IO,_(DIFFIO_RX_T11p,_DIFFOUT_T11p,_DQ2T,_DQ1T,_T_DQ_29,_T_DQ_29)_C21") (pintype "bidirectional"))
    )
    (net (code "171") (name "unconnected-(D4G-IO,_(DIFFIO_RX_T13n,_DIFFOUT_T13n,_DQSn2T,_DQ1T,_T_DQS#_3,_T_DQS#_3)-PadJ19)") (class "Default")
      (node (ref "D4") (pin "J19") (pinfunction "IO,_(DIFFIO_RX_T13n,_DIFFOUT_T13n,_DQSn2T,_DQ1T,_T_DQS#_3,_T_DQS#_3)_J19") (pintype "bidirectional"))
    )
    (net (code "172") (name "unconnected-(D4G-IO,_(DIFFIO_RX_T13p,_DIFFOUT_T13p,_DQS2T,_DQ1T,_T_DQS_3,_T_DQS_3)-PadK20)") (class "Default")
      (node (ref "D4") (pin "K20") (pinfunction "IO,_(DIFFIO_RX_T13p,_DIFFOUT_T13p,_DQS2T,_DQ1T,_T_DQS_3,_T_DQS_3)_K20") (pintype "bidirectional"))
    )
    (net (code "173") (name "unconnected-(D4G-IO,_(DIFFIO_RX_T15n,_DIFFOUT_T15n,_DQ2T,_DQ1T,_T_DQ_24,_T_DQ_24)-PadC19)") (class "Default")
      (node (ref "D4") (pin "C19") (pinfunction "IO,_(DIFFIO_RX_T15n,_DIFFOUT_T15n,_DQ2T,_DQ1T,_T_DQ_24,_T_DQ_24)_C19") (pintype "bidirectional"))
    )
    (net (code "174") (name "unconnected-(D4G-IO,_(DIFFIO_RX_T15p,_DIFFOUT_T15p,_DQ2T,_DQ1T,_T_DQ_25,_T_DQ_25)-PadD20)") (class "Default")
      (node (ref "D4") (pin "D20") (pinfunction "IO,_(DIFFIO_RX_T15p,_DIFFOUT_T15p,_DQ2T,_DQ1T,_T_DQ_25,_T_DQ_25)_D20") (pintype "bidirectional"))
    )
    (net (code "175") (name "unconnected-(D4G-IO,_(DIFFIO_RX_T19n,_DIFFOUT_T19n,_DQ3T,_DQ2T,_T_DQ_20,_T_DQ_20)-PadE18)") (class "Default")
      (node (ref "D4") (pin "E18") (pinfunction "IO,_(DIFFIO_RX_T19n,_DIFFOUT_T19n,_DQ3T,_DQ2T,_T_DQ_20,_T_DQ_20)_E18") (pintype "bidirectional"))
    )
    (net (code "176") (name "unconnected-(D4G-IO,_(DIFFIO_RX_T19p,_DIFFOUT_T19p,_DQ3T,_DQ2T,_T_DQ_21,_T_DQ_21)-PadF19)") (class "Default")
      (node (ref "D4") (pin "F19") (pinfunction "IO,_(DIFFIO_RX_T19p,_DIFFOUT_T19p,_DQ3T,_DQ2T,_T_DQ_21,_T_DQ_21)_F19") (pintype "bidirectional"))
    )
    (net (code "177") (name "unconnected-(D4G-IO,_(DIFFIO_RX_T21n,_DIFFOUT_T21n,_DQSn3T,_DQSn2T,_T_DQS#_2,_T_DQS#_2)-PadK18)") (class "Default")
      (node (ref "D4") (pin "K18") (pinfunction "IO,_(DIFFIO_RX_T21n,_DIFFOUT_T21n,_DQSn3T,_DQSn2T,_T_DQS#_2,_T_DQS#_2)_K18") (pintype "bidirectional"))
    )
    (net (code "178") (name "unconnected-(D4G-IO,_(DIFFIO_RX_T21p,_DIFFOUT_T21p,_DQS3T,_DQS2T,_T_DQS_2,_T_DQS_2)-PadL18)") (class "Default")
      (node (ref "D4") (pin "L18") (pinfunction "IO,_(DIFFIO_RX_T21p,_DIFFOUT_T21p,_DQS3T,_DQS2T,_T_DQS_2,_T_DQS_2)_L18") (pintype "bidirectional"))
    )
    (net (code "179") (name "unconnected-(D4G-IO,_(DIFFIO_RX_T23n,_DIFFOUT_T23n,_DQ3T,_DQ2T,_T_DQ_16,_T_DQ_16)-PadD18)") (class "Default")
      (node (ref "D4") (pin "D18") (pinfunction "IO,_(DIFFIO_RX_T23n,_DIFFOUT_T23n,_DQ3T,_DQ2T,_T_DQ_16,_T_DQ_16)_D18") (pintype "bidirectional"))
    )
    (net (code "180") (name "unconnected-(D4G-IO,_(DIFFIO_RX_T23p,_DIFFOUT_T23p,_DQ3T,_DQ2T,_T_DQ_17,_T_DQ_17)-PadD19)") (class "Default")
      (node (ref "D4") (pin "D19") (pinfunction "IO,_(DIFFIO_RX_T23p,_DIFFOUT_T23p,_DQ3T,_DQ2T,_T_DQ_17,_T_DQ_17)_D19") (pintype "bidirectional"))
    )
    (net (code "181") (name "unconnected-(D4G-IO,_(DIFFIO_TX_T2n,_DIFFOUT_T2n,_DQ1T,_DQ1T,_T_DQ_39,_T_DQ_39)-PadE25)") (class "Default")
      (node (ref "D4") (pin "E25") (pinfunction "IO,_(DIFFIO_TX_T2n,_DIFFOUT_T2n,_DQ1T,_DQ1T,_T_DQ_39,_T_DQ_39)_E25") (pintype "bidirectional"))
    )
    (net (code "182") (name "unconnected-(D4G-IO,_(DIFFIO_TX_T2p,_DIFFOUT_T2p,_DQ1T,_DQ1T,_T_DM_4,_T_DM_4)-PadE26)") (class "Default")
      (node (ref "D4") (pin "E26") (pinfunction "IO,_(DIFFIO_TX_T2p,_DIFFOUT_T2p,_DQ1T,_DQ1T,_T_DM_4,_T_DM_4)_E26") (pintype "bidirectional"))
    )
    (net (code "183") (name "unconnected-(D4G-IO,_(DIFFIO_TX_T4p,_DIFFOUT_T4p,_DQ1T,_DQ1T,_T_DQ_38,_T_DQ_38)-PadC27)") (class "Default")
      (node (ref "D4") (pin "C27") (pinfunction "IO,_(DIFFIO_TX_T4p,_DIFFOUT_T4p,_DQ1T,_DQ1T,_T_DQ_38,_T_DQ_38)_C27") (pintype "bidirectional"))
    )
    (net (code "184") (name "unconnected-(D4G-IO,_(DIFFIO_TX_T6n,_DIFFOUT_T6n,_DQ1T,_DQ1T,_T_DQ_35,_T_DQ_35)-PadA28)") (class "Default")
      (node (ref "D4") (pin "A28") (pinfunction "IO,_(DIFFIO_TX_T6n,_DIFFOUT_T6n,_DQ1T,_DQ1T,_T_DQ_35,_T_DQ_35)_A28") (pintype "bidirectional"))
    )
    (net (code "185") (name "unconnected-(D4G-IO,_(DIFFIO_TX_T8p,_DIFFOUT_T8p,_DQ1T,_DQ1T,_T_DQ_34,_T_DQ_34)-PadB26)") (class "Default")
      (node (ref "D4") (pin "B26") (pinfunction "IO,_(DIFFIO_TX_T8p,_DIFFOUT_T8p,_DQ1T,_DQ1T,_T_DQ_34,_T_DQ_34)_B26") (pintype "bidirectional"))
    )
    (net (code "186") (name "unconnected-(D4G-IO,_(DIFFIO_TX_T10n,_DIFFOUT_T10n,_DQ2T,_DQ1T,_T_DQ_31,_T_DQ_31)-PadC25)") (class "Default")
      (node (ref "D4") (pin "C25") (pinfunction "IO,_(DIFFIO_TX_T10n,_DIFFOUT_T10n,_DQ2T,_DQ1T,_T_DQ_31,_T_DQ_31)_C25") (pintype "bidirectional"))
    )
    (net (code "187") (name "unconnected-(D4G-IO,_(DIFFIO_TX_T10p,_DIFFOUT_T10p,_DQ2T,_DQ1T,_T_DM_3,_T_DM_3)-PadD25)") (class "Default")
      (node (ref "D4") (pin "D25") (pinfunction "IO,_(DIFFIO_TX_T10p,_DIFFOUT_T10p,_DQ2T,_DQ1T,_T_DM_3,_T_DM_3)_D25") (pintype "bidirectional"))
    )
    (net (code "188") (name "unconnected-(D4G-IO,_(DIFFIO_TX_T12p,_DIFFOUT_T12p,_DQ2T,_DQ1T,_T_DQ_30,_T_DQ_30)-PadD23)") (class "Default")
      (node (ref "D4") (pin "D23") (pinfunction "IO,_(DIFFIO_TX_T12p,_DIFFOUT_T12p,_DQ2T,_DQ1T,_T_DQ_30,_T_DQ_30)_D23") (pintype "bidirectional"))
    )
    (net (code "189") (name "unconnected-(D4G-IO,_(DIFFIO_TX_T14n,_DIFFOUT_T14n,_DQ2T,_DQ1T,_T_DQ_27,_T_DQ_27)-PadD22)") (class "Default")
      (node (ref "D4") (pin "D22") (pinfunction "IO,_(DIFFIO_TX_T14n,_DIFFOUT_T14n,_DQ2T,_DQ1T,_T_DQ_27,_T_DQ_27)_D22") (pintype "bidirectional"))
    )
    (net (code "190") (name "unconnected-(D4G-IO,_(DIFFIO_TX_T16p,_DIFFOUT_T16p,_DQ2T,_DQ1T,_T_DQ_26,_T_DQ_26)-PadA25)") (class "Default")
      (node (ref "D4") (pin "A25") (pinfunction "IO,_(DIFFIO_TX_T16p,_DIFFOUT_T16p,_DQ2T,_DQ1T,_T_DQ_26,_T_DQ_26)_A25") (pintype "bidirectional"))
    )
    (net (code "191") (name "unconnected-(D4G-IO,_(DIFFIO_TX_T18n,_DIFFOUT_T18n,_DQ3T,_DQ2T,_T_DQ_23,_T_DQ_23)-PadB24)") (class "Default")
      (node (ref "D4") (pin "B24") (pinfunction "IO,_(DIFFIO_TX_T18n,_DIFFOUT_T18n,_DQ3T,_DQ2T,_T_DQ_23,_T_DQ_23)_B24") (pintype "bidirectional"))
    )
    (net (code "192") (name "unconnected-(D4G-IO,_(DIFFIO_TX_T18p,_DIFFOUT_T18p,_DQ3T,_DQ2T,_T_DM_2,_T_DM_2)-PadC24)") (class "Default")
      (node (ref "D4") (pin "C24") (pinfunction "IO,_(DIFFIO_TX_T18p,_DIFFOUT_T18p,_DQ3T,_DQ2T,_T_DM_2,_T_DM_2)_C24") (pintype "bidirectional"))
    )
    (net (code "193") (name "unconnected-(D4G-IO,_(DIFFIO_TX_T20p,_DIFFOUT_T20p,_DQ3T,_DQ2T,_T_DQ_22,_T_DQ_22)-PadB23)") (class "Default")
      (node (ref "D4") (pin "B23") (pinfunction "IO,_(DIFFIO_TX_T20p,_DIFFOUT_T20p,_DQ3T,_DQ2T,_T_DQ_22,_T_DQ_22)_B23") (pintype "bidirectional"))
    )
    (net (code "194") (name "unconnected-(D4G-IO,_(DIFFIO_TX_T22n,_DIFFOUT_T22n,_DQ3T,_DQ2T,_T_DQ_19,_T_DQ_19)-PadB21)") (class "Default")
      (node (ref "D4") (pin "B21") (pinfunction "IO,_(DIFFIO_TX_T22n,_DIFFOUT_T22n,_DQ3T,_DQ2T,_T_DQ_19,_T_DQ_19)_B21") (pintype "bidirectional"))
    )
    (net (code "195") (name "unconnected-(D4G-IO,_(DIFFIO_TX_T24p,_DIFFOUT_T24p,_DQ3T,_DQ2T,_T_DQ_18,_T_DQ_18)-PadA21)") (class "Default")
      (node (ref "D4") (pin "A21") (pinfunction "IO,_(DIFFIO_TX_T24p,_DIFFOUT_T24p,_DQ3T,_DQ2T,_T_DQ_18,_T_DQ_18)_A21") (pintype "bidirectional"))
    )
    (net (code "196") (name "unconnected-(D4G-IO,_(DIFFIO_TX_T30p,_DIFFOUT_T30p,__,__,_T_CKE_1,_T_CKE_1)-PadD14)") (class "Default")
      (node (ref "D4") (pin "D14") (pinfunction "IO,_(DIFFIO_TX_T30p,_DIFFOUT_T30p,__,__,_T_CKE_1,_T_CKE_1)_D14") (pintype "bidirectional"))
    )
    (net (code "197") (name "unconnected-(D4G-IO,_(DIFFIO_TX_T36n,_DIFFOUT_T36n,_DQ5T,__,_T_ODT_1,_T_ODT_1)-PadC12)") (class "Default")
      (node (ref "D4") (pin "C12") (pinfunction "IO,_(DIFFIO_TX_T36n,_DIFFOUT_T36n,_DQ5T,__,_T_ODT_1,_T_ODT_1)_C12") (pintype "bidirectional"))
    )
    (net (code "198") (name "unconnected-(D4G-IO,_CLK10n,_(DIFFIO_RX_T33n,_DIFFOUT_T33n)-PadG17)") (class "Default")
      (node (ref "D4") (pin "G17") (pinfunction "IO,_CLK10n,_(DIFFIO_RX_T33n,_DIFFOUT_T33n)_G17") (pintype "bidirectional"))
    )
    (net (code "199") (name "unconnected-(D4G-IO,_CLK10p,_(DIFFIO_RX_T33p,_DIFFOUT_T33p)-PadH17)") (class "Default")
      (node (ref "D4") (pin "H17") (pinfunction "IO,_CLK10p,_(DIFFIO_RX_T33p,_DIFFOUT_T33p)_H17") (pintype "bidirectional"))
    )
    (net (code "200") (name "unconnected-(D4G-IO,_CLK11n,_(DIFFIO_RX_T25n,_DIFFOUT_T25n)-PadJ18)") (class "Default")
      (node (ref "D4") (pin "J18") (pinfunction "IO,_CLK11n,_(DIFFIO_RX_T25n,_DIFFOUT_T25n)_J18") (pintype "bidirectional"))
    )
    (net (code "201") (name "unconnected-(D4G-IO,_CLK11p,_(DIFFIO_RX_T25p,_DIFFOUT_T25p)-PadH19)") (class "Default")
      (node (ref "D4") (pin "H19") (pinfunction "IO,_CLK11p,_(DIFFIO_RX_T25p,_DIFFOUT_T25p)_H19") (pintype "bidirectional"))
    )
    (net (code "202") (name "unconnected-(D4H-IO,_(DIFFIO_RX_T53n,_DIFFOUT_T53n,_DQSn7T,__,_T_CS#_1,_T_CS#_1)-PadH15)") (class "Default")
      (node (ref "D4") (pin "H15") (pinfunction "IO,_(DIFFIO_RX_T53n,_DIFFOUT_T53n,_DQSn7T,__,_T_CS#_1,_T_CS#_1)_H15") (pintype "bidirectional"))
    )
    (net (code "203") (name "unconnected-(D4H-IO,_(DIFFIO_RX_T55n,_DIFFOUT_T55n,_DQ7T,__,_T_A_15)-PadD10)") (class "Default")
      (node (ref "D4") (pin "D10") (pinfunction "IO,_(DIFFIO_RX_T55n,_DIFFOUT_T55n,_DQ7T,__,_T_A_15)_D10") (pintype "bidirectional"))
    )
    (net (code "204") (name "unconnected-(D4H-IO,_(DIFFIO_RX_T57n,_DIFFOUT_T57n)-PadL9)") (class "Default")
      (node (ref "D4") (pin "L9") (pinfunction "IO,_(DIFFIO_RX_T57n,_DIFFOUT_T57n)_L9") (pintype "bidirectional"))
    )
    (net (code "205") (name "unconnected-(D4H-IO,_(DIFFIO_RX_T57p,_DIFFOUT_T57p)-PadL10)") (class "Default")
      (node (ref "D4") (pin "L10") (pinfunction "IO,_(DIFFIO_RX_T57p,_DIFFOUT_T57p)_L10") (pintype "bidirectional"))
    )
    (net (code "206") (name "unconnected-(D4H-IO,_(DIFFIO_RX_T59n,_DIFFOUT_T59n,_DQ8T)-PadF14)") (class "Default")
      (node (ref "D4") (pin "F14") (pinfunction "IO,_(DIFFIO_RX_T59n,_DIFFOUT_T59n,_DQ8T)_F14") (pintype "bidirectional"))
    )
    (net (code "207") (name "unconnected-(D4H-IO,_(DIFFIO_RX_T59p,_DIFFOUT_T59p,_DQ8T)-PadG14)") (class "Default")
      (node (ref "D4") (pin "G14") (pinfunction "IO,_(DIFFIO_RX_T59p,_DIFFOUT_T59p,_DQ8T)_G14") (pintype "bidirectional"))
    )
    (net (code "208") (name "unconnected-(D4H-IO,_(DIFFIO_RX_T61n,_DIFFOUT_T61n,_DQSn8T)-PadH14)") (class "Default")
      (node (ref "D4") (pin "H14") (pinfunction "IO,_(DIFFIO_RX_T61n,_DIFFOUT_T61n,_DQSn8T)_H14") (pintype "bidirectional"))
    )
    (net (code "209") (name "unconnected-(D4H-IO,_(DIFFIO_RX_T61p,_DIFFOUT_T61p,_DQS8T)-PadJ14)") (class "Default")
      (node (ref "D4") (pin "J14") (pinfunction "IO,_(DIFFIO_RX_T61p,_DIFFOUT_T61p,_DQS8T)_J14") (pintype "bidirectional"))
    )
    (net (code "210") (name "unconnected-(D4H-IO,_(DIFFIO_RX_T63n,_DIFFOUT_T63n,_DQ8T)-PadK11)") (class "Default")
      (node (ref "D4") (pin "K11") (pinfunction "IO,_(DIFFIO_RX_T63n,_DIFFOUT_T63n,_DQ8T)_K11") (pintype "bidirectional"))
    )
    (net (code "211") (name "unconnected-(D4H-IO,_(DIFFIO_RX_T63p,_DIFFOUT_T63p,_DQ8T)-PadL11)") (class "Default")
      (node (ref "D4") (pin "L11") (pinfunction "IO,_(DIFFIO_RX_T63p,_DIFFOUT_T63p,_DQ8T)_L11") (pintype "bidirectional"))
    )
    (net (code "212") (name "unconnected-(D4H-IO,_(DIFFIO_RX_T65n,_DIFFOUT_T65n)-PadN12)") (class "Default")
      (node (ref "D4") (pin "N12") (pinfunction "IO,_(DIFFIO_RX_T65n,_DIFFOUT_T65n)_N12") (pintype "bidirectional"))
    )
    (net (code "213") (name "unconnected-(D4H-IO,_(DIFFIO_RX_T65p,_DIFFOUT_T65p)-PadP12)") (class "Default")
      (node (ref "D4") (pin "P12") (pinfunction "IO,_(DIFFIO_RX_T65p,_DIFFOUT_T65p)_P12") (pintype "bidirectional"))
    )
    (net (code "214") (name "unconnected-(D4H-IO,_(DIFFIO_RX_T67n,_DIFFOUT_T67n,_DQ9T,_DQ3T)-PadG12)") (class "Default")
      (node (ref "D4") (pin "G12") (pinfunction "IO,_(DIFFIO_RX_T67n,_DIFFOUT_T67n,_DQ9T,_DQ3T)_G12") (pintype "bidirectional"))
    )
    (net (code "215") (name "unconnected-(D4H-IO,_(DIFFIO_RX_T67p,_DIFFOUT_T67p,_DQ9T,_DQ3T)-PadH12)") (class "Default")
      (node (ref "D4") (pin "H12") (pinfunction "IO,_(DIFFIO_RX_T67p,_DIFFOUT_T67p,_DQ9T,_DQ3T)_H12") (pintype "bidirectional"))
    )
    (net (code "216") (name "unconnected-(D4H-IO,_(DIFFIO_RX_T69n,_DIFFOUT_T69n,_DQSn9T,_DQSn3T)-PadJ13)") (class "Default")
      (node (ref "D4") (pin "J13") (pinfunction "IO,_(DIFFIO_RX_T69n,_DIFFOUT_T69n,_DQSn9T,_DQSn3T)_J13") (pintype "bidirectional"))
    )
    (net (code "217") (name "unconnected-(D4H-IO,_(DIFFIO_RX_T69p,_DIFFOUT_T69p,_DQS9T,_DQS3T)-PadK13)") (class "Default")
      (node (ref "D4") (pin "K13") (pinfunction "IO,_(DIFFIO_RX_T69p,_DIFFOUT_T69p,_DQS9T,_DQS3T)_K13") (pintype "bidirectional"))
    )
    (net (code "218") (name "unconnected-(D4H-IO,_(DIFFIO_RX_T71n,_DIFFOUT_T71n,_DQ9T,_DQ3T)-PadN11)") (class "Default")
      (node (ref "D4") (pin "N11") (pinfunction "IO,_(DIFFIO_RX_T71n,_DIFFOUT_T71n,_DQ9T,_DQ3T)_N11") (pintype "bidirectional"))
    )
    (net (code "219") (name "unconnected-(D4H-IO,_(DIFFIO_RX_T71p,_DIFFOUT_T71p,_DQ9T,_DQ3T)-PadP10)") (class "Default")
      (node (ref "D4") (pin "P10") (pinfunction "IO,_(DIFFIO_RX_T71p,_DIFFOUT_T71p,_DQ9T,_DQ3T)_P10") (pintype "bidirectional"))
    )
    (net (code "220") (name "unconnected-(D4H-IO,_(DIFFIO_RX_T73n,_DIFFOUT_T73n)-PadR11)") (class "Default")
      (node (ref "D4") (pin "R11") (pinfunction "IO,_(DIFFIO_RX_T73n,_DIFFOUT_T73n)_R11") (pintype "bidirectional"))
    )
    (net (code "221") (name "unconnected-(D4H-IO,_(DIFFIO_RX_T73p,_DIFFOUT_T73p)-PadR12)") (class "Default")
      (node (ref "D4") (pin "R12") (pinfunction "IO,_(DIFFIO_RX_T73p,_DIFFOUT_T73p)_R12") (pintype "bidirectional"))
    )
    (net (code "222") (name "unconnected-(D4H-IO,_(DIFFIO_RX_T75n,_DIFFOUT_T75n,_DQ10T,_DQ3T)-PadJ12)") (class "Default")
      (node (ref "D4") (pin "J12") (pinfunction "IO,_(DIFFIO_RX_T75n,_DIFFOUT_T75n,_DQ10T,_DQ3T)_J12") (pintype "bidirectional"))
    )
    (net (code "223") (name "unconnected-(D4H-IO,_(DIFFIO_RX_T75p,_DIFFOUT_T75p,_DQ10T,_DQ3T)-PadK12)") (class "Default")
      (node (ref "D4") (pin "K12") (pinfunction "IO,_(DIFFIO_RX_T75p,_DIFFOUT_T75p,_DQ10T,_DQ3T)_K12") (pintype "bidirectional"))
    )
    (net (code "224") (name "unconnected-(D4H-IO,_(DIFFIO_RX_T77n,_DIFFOUT_T77n,_DQSn10T,_DQ3T)-PadN9)") (class "Default")
      (node (ref "D4") (pin "N9") (pinfunction "IO,_(DIFFIO_RX_T77n,_DIFFOUT_T77n,_DQSn10T,_DQ3T)_N9") (pintype "bidirectional"))
    )
    (net (code "225") (name "unconnected-(D4H-IO,_(DIFFIO_RX_T77p,_DIFFOUT_T77p,_DQS10T,_DQ3T)-PadN10)") (class "Default")
      (node (ref "D4") (pin "N10") (pinfunction "IO,_(DIFFIO_RX_T77p,_DIFFOUT_T77p,_DQS10T,_DQ3T)_N10") (pintype "bidirectional"))
    )
    (net (code "226") (name "unconnected-(D4H-IO,_(DIFFIO_RX_T79n,_DIFFOUT_T79n,_DQ10T,_DQ3T)-PadM11)") (class "Default")
      (node (ref "D4") (pin "M11") (pinfunction "IO,_(DIFFIO_RX_T79n,_DIFFOUT_T79n,_DQ10T,_DQ3T)_M11") (pintype "bidirectional"))
    )
    (net (code "227") (name "unconnected-(D4H-IO,_(DIFFIO_RX_T79p,_DIFFOUT_T79p,_DQ10T,_DQ3T)-PadM12)") (class "Default")
      (node (ref "D4") (pin "M12") (pinfunction "IO,_(DIFFIO_RX_T79p,_DIFFOUT_T79p,_DQ10T,_DQ3T)_M12") (pintype "bidirectional"))
    )
    (net (code "228") (name "unconnected-(D4H-IO,_(DIFFIO_TX_T58n,_DIFFOUT_T58n,_DQ8T)-PadE13)") (class "Default")
      (node (ref "D4") (pin "E13") (pinfunction "IO,_(DIFFIO_TX_T58n,_DIFFOUT_T58n,_DQ8T)_E13") (pintype "bidirectional"))
    )
    (net (code "229") (name "unconnected-(D4H-IO,_(DIFFIO_TX_T58p,_DIFFOUT_T58p,_DQ8T)-PadF13)") (class "Default")
      (node (ref "D4") (pin "F13") (pinfunction "IO,_(DIFFIO_TX_T58p,_DIFFOUT_T58p,_DQ8T)_F13") (pintype "bidirectional"))
    )
    (net (code "230") (name "unconnected-(D4H-IO,_(DIFFIO_TX_T60n,_DIFFOUT_T60n,_DQ8T)-PadA4)") (class "Default")
      (node (ref "D4") (pin "A4") (pinfunction "IO,_(DIFFIO_TX_T60n,_DIFFOUT_T60n,_DQ8T)_A4") (pintype "bidirectional"))
    )
    (net (code "231") (name "unconnected-(D4H-IO,_(DIFFIO_TX_T60p,_DIFFOUT_T60p,_DQ8T)-PadA5)") (class "Default")
      (node (ref "D4") (pin "A5") (pinfunction "IO,_(DIFFIO_TX_T60p,_DIFFOUT_T60p,_DQ8T)_A5") (pintype "bidirectional"))
    )
    (net (code "232") (name "unconnected-(D4H-IO,_(DIFFIO_TX_T62n,_DIFFOUT_T62n,_DQ8T)-PadH7)") (class "Default")
      (node (ref "D4") (pin "H7") (pinfunction "IO,_(DIFFIO_TX_T62n,_DIFFOUT_T62n,_DQ8T)_H7") (pintype "bidirectional"))
    )
    (net (code "233") (name "unconnected-(D4H-IO,_(DIFFIO_TX_T62p,_DIFFOUT_T62p)-PadJ7)") (class "Default")
      (node (ref "D4") (pin "J7") (pinfunction "IO,_(DIFFIO_TX_T62p,_DIFFOUT_T62p)_J7") (pintype "bidirectional"))
    )
    (net (code "234") (name "unconnected-(D4H-IO,_(DIFFIO_TX_T64n,_DIFFOUT_T64n)-PadH9)") (class "Default")
      (node (ref "D4") (pin "H9") (pinfunction "IO,_(DIFFIO_TX_T64n,_DIFFOUT_T64n)_H9") (pintype "bidirectional"))
    )
    (net (code "235") (name "unconnected-(D4H-IO,_(DIFFIO_TX_T64p,_DIFFOUT_T64p,_DQ8T)-PadJ9)") (class "Default")
      (node (ref "D4") (pin "J9") (pinfunction "IO,_(DIFFIO_TX_T64p,_DIFFOUT_T64p,_DQ8T)_J9") (pintype "bidirectional"))
    )
    (net (code "236") (name "unconnected-(D4H-IO,_(DIFFIO_TX_T66n,_DIFFOUT_T66n,_DQ9T,_DQ3T)-PadF8)") (class "Default")
      (node (ref "D4") (pin "F8") (pinfunction "IO,_(DIFFIO_TX_T66n,_DIFFOUT_T66n,_DQ9T,_DQ3T)_F8") (pintype "bidirectional"))
    )
    (net (code "237") (name "unconnected-(D4H-IO,_(DIFFIO_TX_T66p,_DIFFOUT_T66p,_DQ9T,_DQ3T)-PadG9)") (class "Default")
      (node (ref "D4") (pin "G9") (pinfunction "IO,_(DIFFIO_TX_T66p,_DIFFOUT_T66p,_DQ9T,_DQ3T)_G9") (pintype "bidirectional"))
    )
    (net (code "238") (name "unconnected-(D4H-IO,_(DIFFIO_TX_T68n,_DIFFOUT_T68n,_DQ9T,_DQ3T)-PadD8)") (class "Default")
      (node (ref "D4") (pin "D8") (pinfunction "IO,_(DIFFIO_TX_T68n,_DIFFOUT_T68n,_DQ9T,_DQ3T)_D8") (pintype "bidirectional"))
    )
    (net (code "239") (name "unconnected-(D4H-IO,_(DIFFIO_TX_T68p,_DIFFOUT_T68p,_DQ9T,_DQ3T)-PadE8)") (class "Default")
      (node (ref "D4") (pin "E8") (pinfunction "IO,_(DIFFIO_TX_T68p,_DIFFOUT_T68p,_DQ9T,_DQ3T)_E8") (pintype "bidirectional"))
    )
    (net (code "240") (name "unconnected-(D4H-IO,_(DIFFIO_TX_T70n,_DIFFOUT_T70n,_DQ9T,_DQ3T)-PadA2)") (class "Default")
      (node (ref "D4") (pin "A2") (pinfunction "IO,_(DIFFIO_TX_T70n,_DIFFOUT_T70n,_DQ9T,_DQ3T)_A2") (pintype "bidirectional"))
    )
    (net (code "241") (name "unconnected-(D4H-IO,_(DIFFIO_TX_T70p,_DIFFOUT_T70p)-PadA3)") (class "Default")
      (node (ref "D4") (pin "A3") (pinfunction "IO,_(DIFFIO_TX_T70p,_DIFFOUT_T70p)_A3") (pintype "bidirectional"))
    )
    (net (code "242") (name "unconnected-(D4H-IO,_(DIFFIO_TX_T72n,_DIFFOUT_T72n)-PadD6)") (class "Default")
      (node (ref "D4") (pin "D6") (pinfunction "IO,_(DIFFIO_TX_T72n,_DIFFOUT_T72n)_D6") (pintype "bidirectional"))
    )
    (net (code "243") (name "unconnected-(D4H-IO,_(DIFFIO_TX_T72p,_DIFFOUT_T72p,_DQ9T,_DQ3T)-PadD7)") (class "Default")
      (node (ref "D4") (pin "D7") (pinfunction "IO,_(DIFFIO_TX_T72p,_DIFFOUT_T72p,_DQ9T,_DQ3T)_D7") (pintype "bidirectional"))
    )
    (net (code "244") (name "unconnected-(D4H-IO,_(DIFFIO_TX_T74n,_DIFFOUT_T74n,_DQ10T,_DQ3T)-PadE6)") (class "Default")
      (node (ref "D4") (pin "E6") (pinfunction "IO,_(DIFFIO_TX_T74n,_DIFFOUT_T74n,_DQ10T,_DQ3T)_E6") (pintype "bidirectional"))
    )
    (net (code "245") (name "unconnected-(D4H-IO,_(DIFFIO_TX_T74p,_DIFFOUT_T74p,_DQ10T,_DQ3T)-PadE7)") (class "Default")
      (node (ref "D4") (pin "E7") (pinfunction "IO,_(DIFFIO_TX_T74p,_DIFFOUT_T74p,_DQ10T,_DQ3T)_E7") (pintype "bidirectional"))
    )
    (net (code "246") (name "unconnected-(D4H-IO,_(DIFFIO_TX_T76n,_DIFFOUT_T76n,_DQ10T,_DQ3T)-PadJ10)") (class "Default")
      (node (ref "D4") (pin "J10") (pinfunction "IO,_(DIFFIO_TX_T76n,_DIFFOUT_T76n,_DQ10T,_DQ3T)_J10") (pintype "bidirectional"))
    )
    (net (code "247") (name "unconnected-(D4H-IO,_(DIFFIO_TX_T76p,_DIFFOUT_T76p,_DQ10T,_DQ3T)-PadK10)") (class "Default")
      (node (ref "D4") (pin "K10") (pinfunction "IO,_(DIFFIO_TX_T76p,_DIFFOUT_T76p,_DQ10T,_DQ3T)_K10") (pintype "bidirectional"))
    )
    (net (code "248") (name "unconnected-(D4H-IO,_(DIFFIO_TX_T78n,_DIFFOUT_T78n,_DQ10T,_DQ3T)-PadF6)") (class "Default")
      (node (ref "D4") (pin "F6") (pinfunction "IO,_(DIFFIO_TX_T78n,_DIFFOUT_T78n,_DQ10T,_DQ3T)_F6") (pintype "bidirectional"))
    )
    (net (code "249") (name "unconnected-(D4H-IO,_(DIFFIO_TX_T78p,_DIFFOUT_T78p)-PadG6)") (class "Default")
      (node (ref "D4") (pin "G6") (pinfunction "IO,_(DIFFIO_TX_T78p,_DIFFOUT_T78p)_G6") (pintype "bidirectional"))
    )
    (net (code "250") (name "unconnected-(D4H-IO,_(DIFFIO_TX_T80n,_DIFFOUT_T80n)-PadG7)") (class "Default")
      (node (ref "D4") (pin "G7") (pinfunction "IO,_(DIFFIO_TX_T80n,_DIFFOUT_T80n)_G7") (pintype "bidirectional"))
    )
    (net (code "251") (name "unconnected-(D4H-IO,_(DIFFIO_TX_T80p,_DIFFOUT_T80p,_DQ10T,_DQ3T)-PadG8)") (class "Default")
      (node (ref "D4") (pin "G8") (pinfunction "IO,_(DIFFIO_TX_T80p,_DIFFOUT_T80p,_DQ10T,_DQ3T)_G8") (pintype "bidirectional"))
    )
    (net (code "252") (name "unconnected-(D4H-IO,_CLK8n,_FPLL_TL_FBn,_(DIFFIO_RX_T49n,_DIFFOUT_T49n)-PadL13)") (class "Default")
      (node (ref "D4") (pin "L13") (pinfunction "IO,_CLK8n,_FPLL_TL_FBn,_(DIFFIO_RX_T49n,_DIFFOUT_T49n)_L13") (pintype "bidirectional"))
    )
    (net (code "253") (name "unconnected-(D4H-IO,_CLK8p,_FPLL_TL_FBp,_(DIFFIO_RX_T49p,_DIFFOUT_T49p)-PadL14)") (class "Default")
      (node (ref "D4") (pin "L14") (pinfunction "IO,_CLK8p,_FPLL_TL_FBp,_(DIFFIO_RX_T49p,_DIFFOUT_T49p)_L14") (pintype "bidirectional"))
    )
    (net (code "254") (name "unconnected-(D4H-IO,_CLK9n,_(DIFFIO_RX_T41n,_DIFFOUT_T41n)-PadK15)") (class "Default")
      (node (ref "D4") (pin "K15") (pinfunction "IO,_CLK9n,_(DIFFIO_RX_T41n,_DIFFOUT_T41n)_K15") (pintype "bidirectional"))
    )
    (net (code "255") (name "unconnected-(D4H-IO,_CLK9p,_(DIFFIO_RX_T41p,_DIFFOUT_T41p)-PadL15)") (class "Default")
      (node (ref "D4") (pin "L15") (pinfunction "IO,_CLK9p,_(DIFFIO_RX_T41p,_DIFFOUT_T41p)_L15") (pintype "bidirectional"))
    )
  )
)
